# Pi_Supply_Smart_LoRa_Gateway.net
KiCad netlist of a schematic drawn in EAGLE
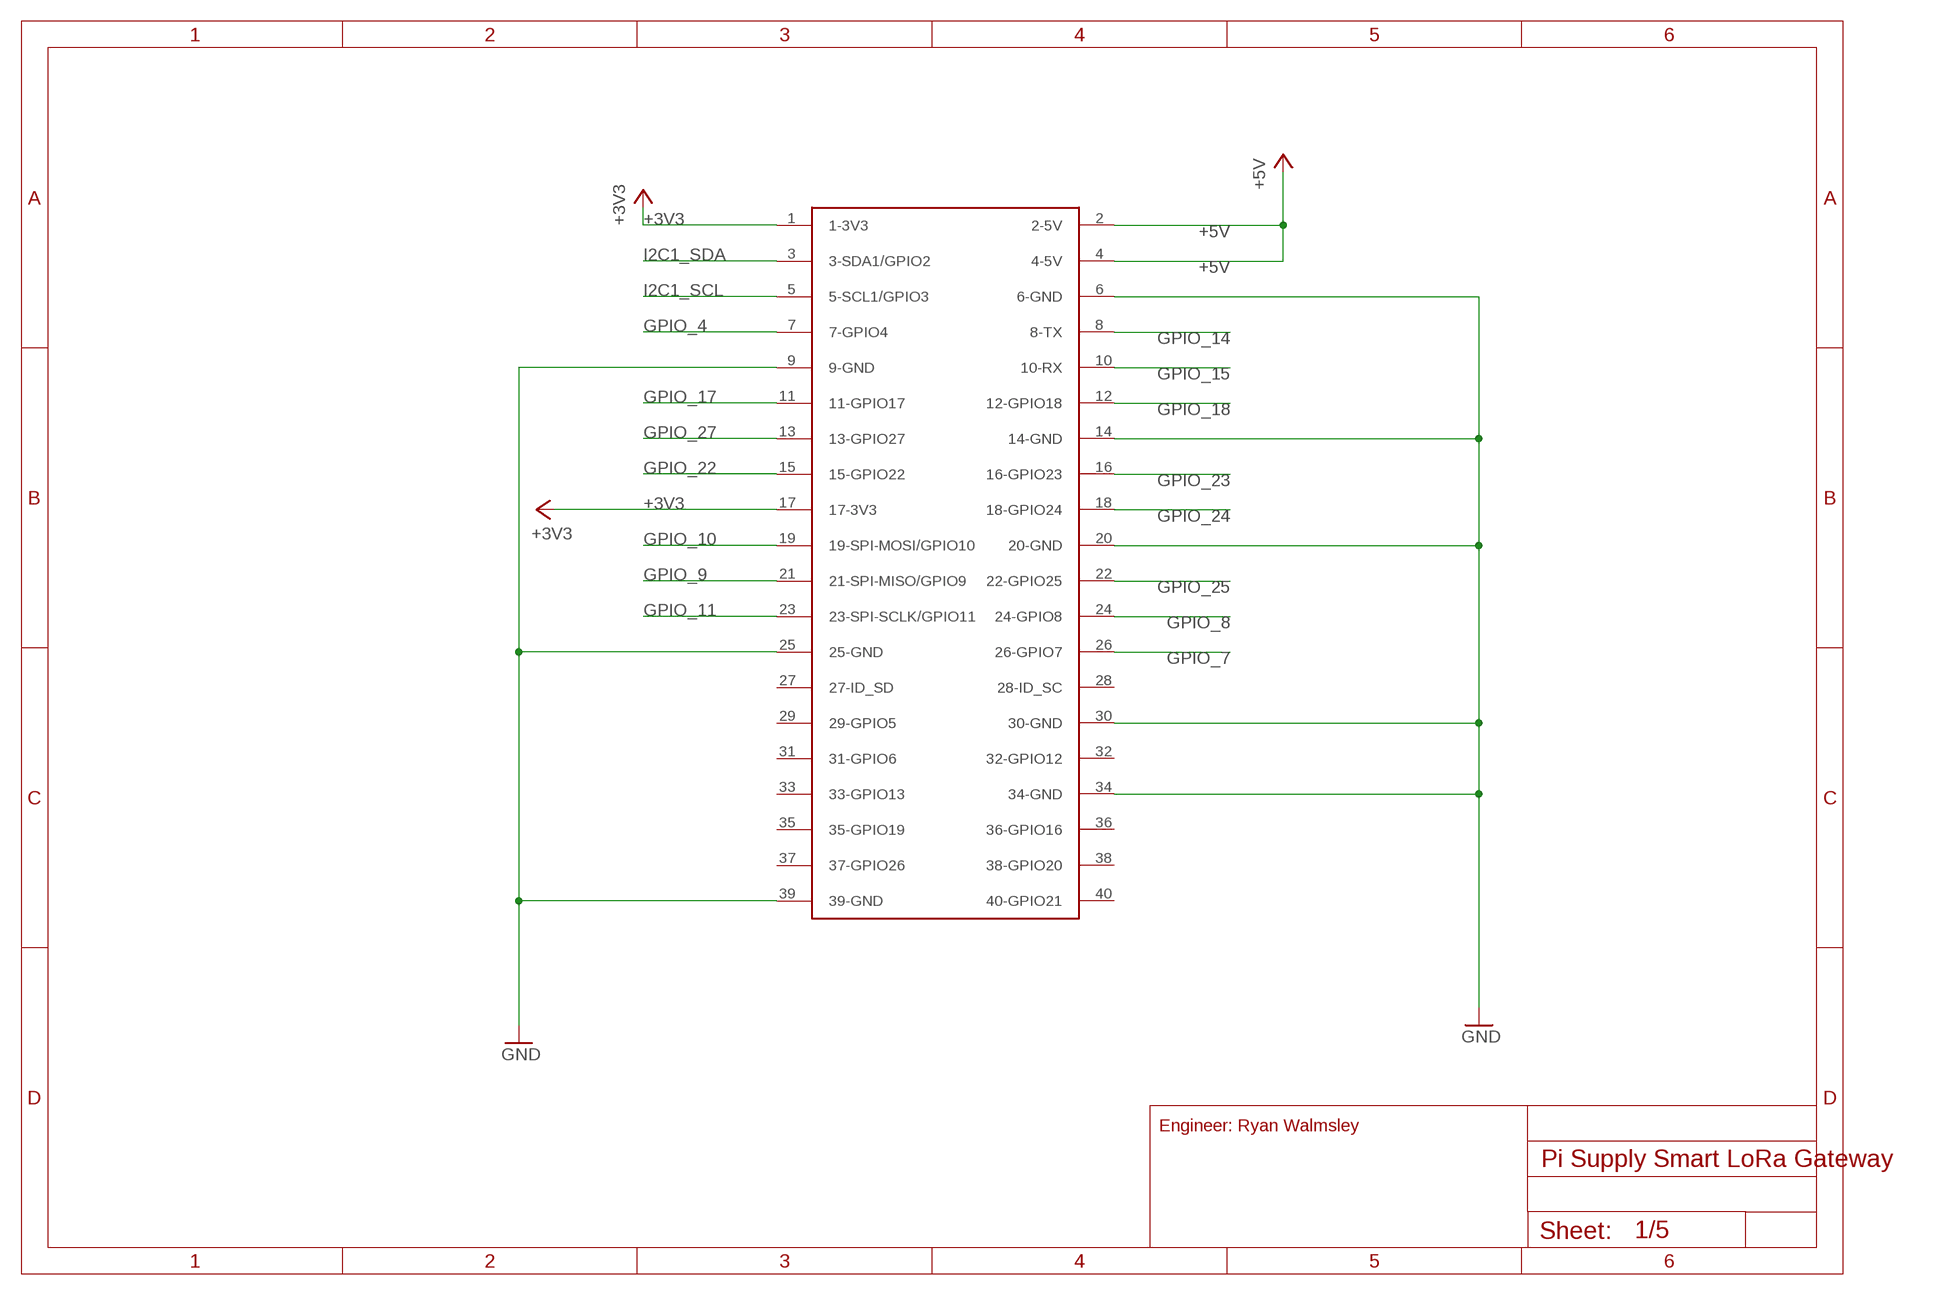
[diagram p0: schematic, sheet 1]
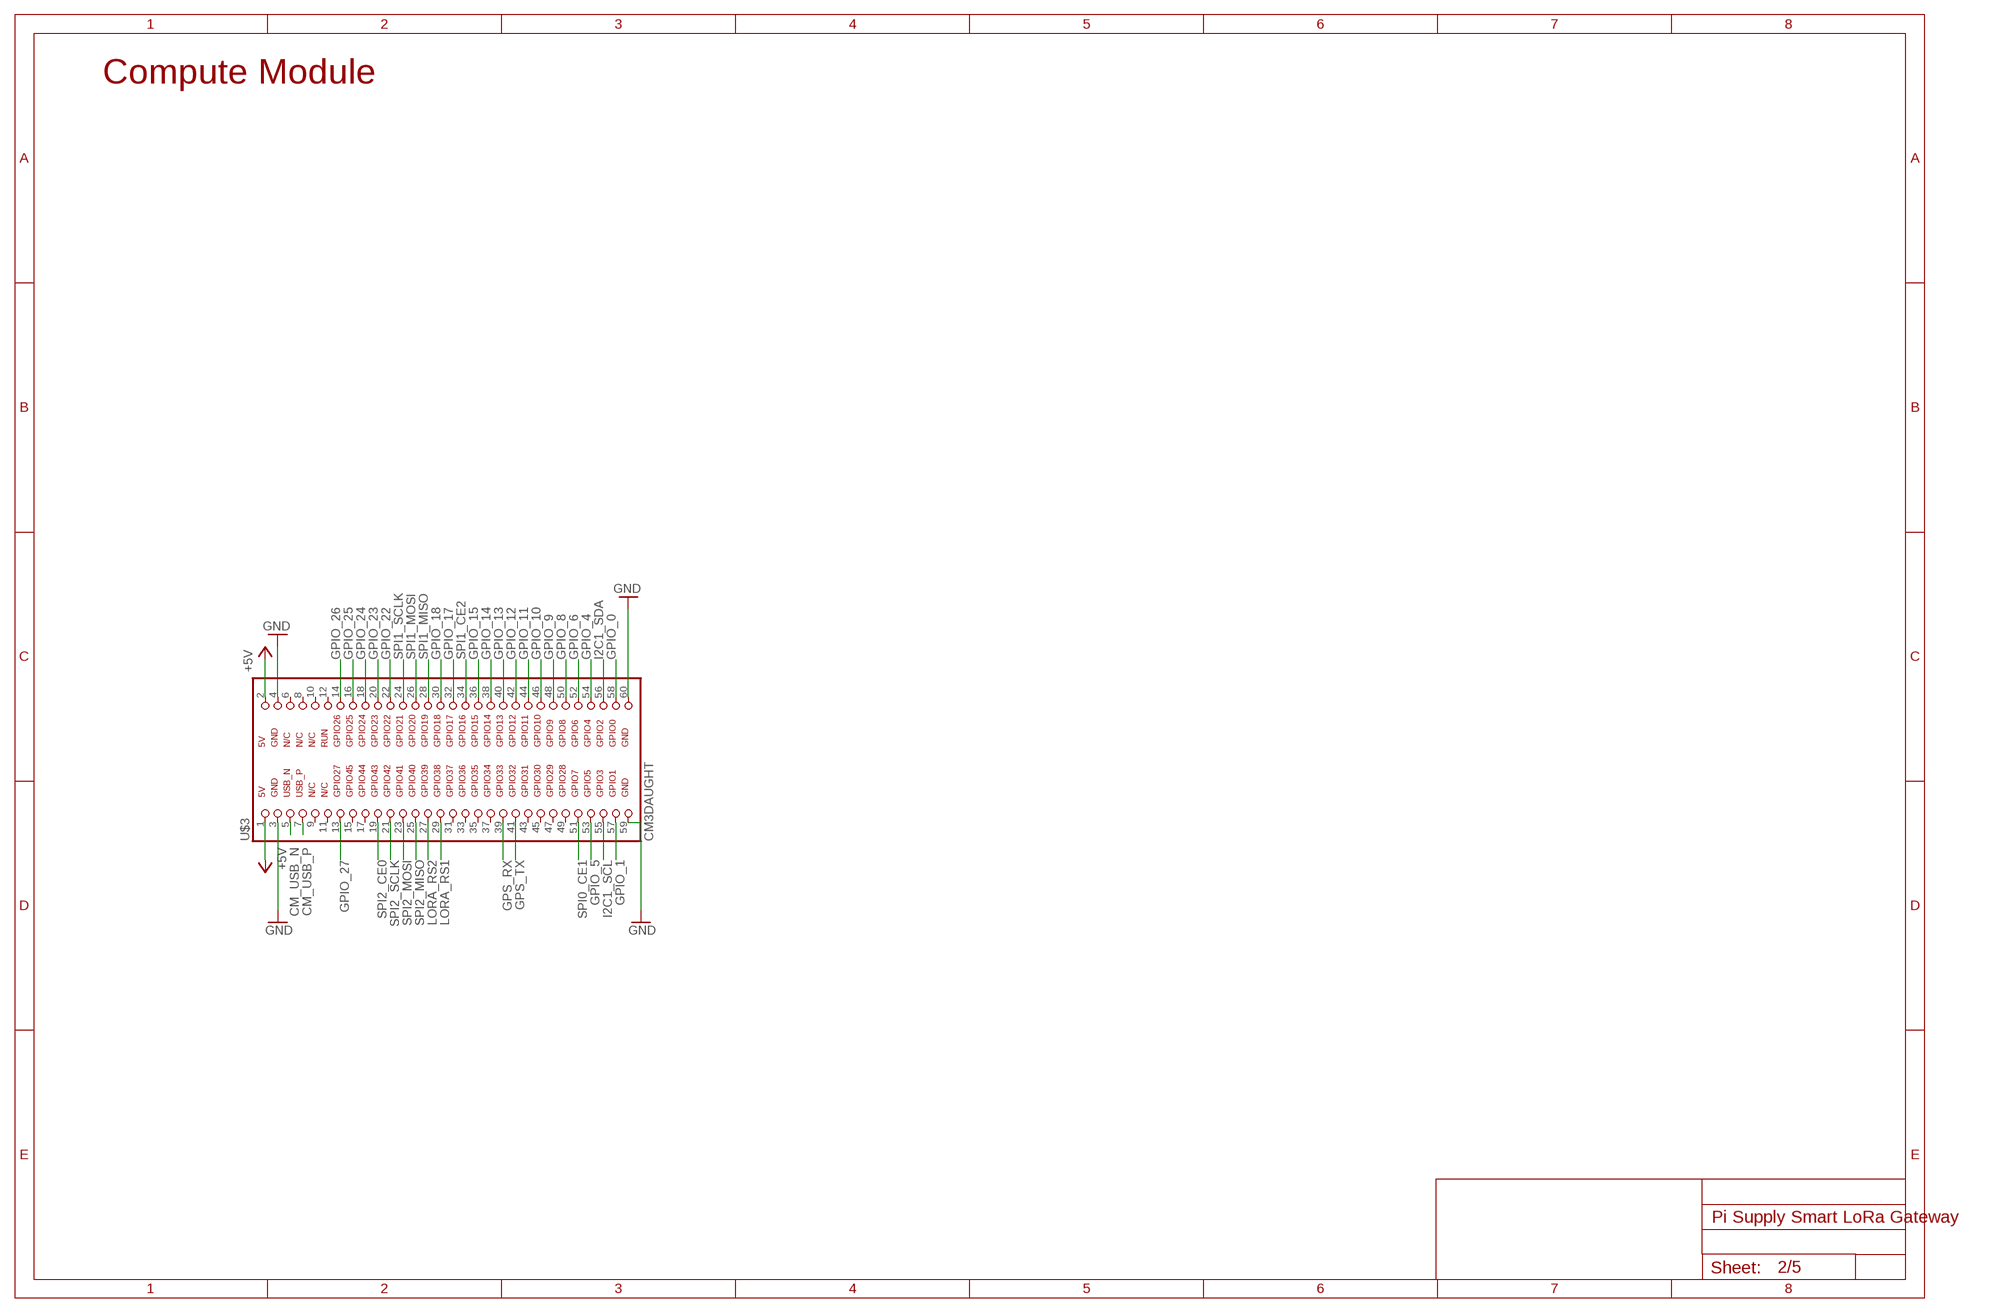
[diagram p1: schematic, sheet 2]
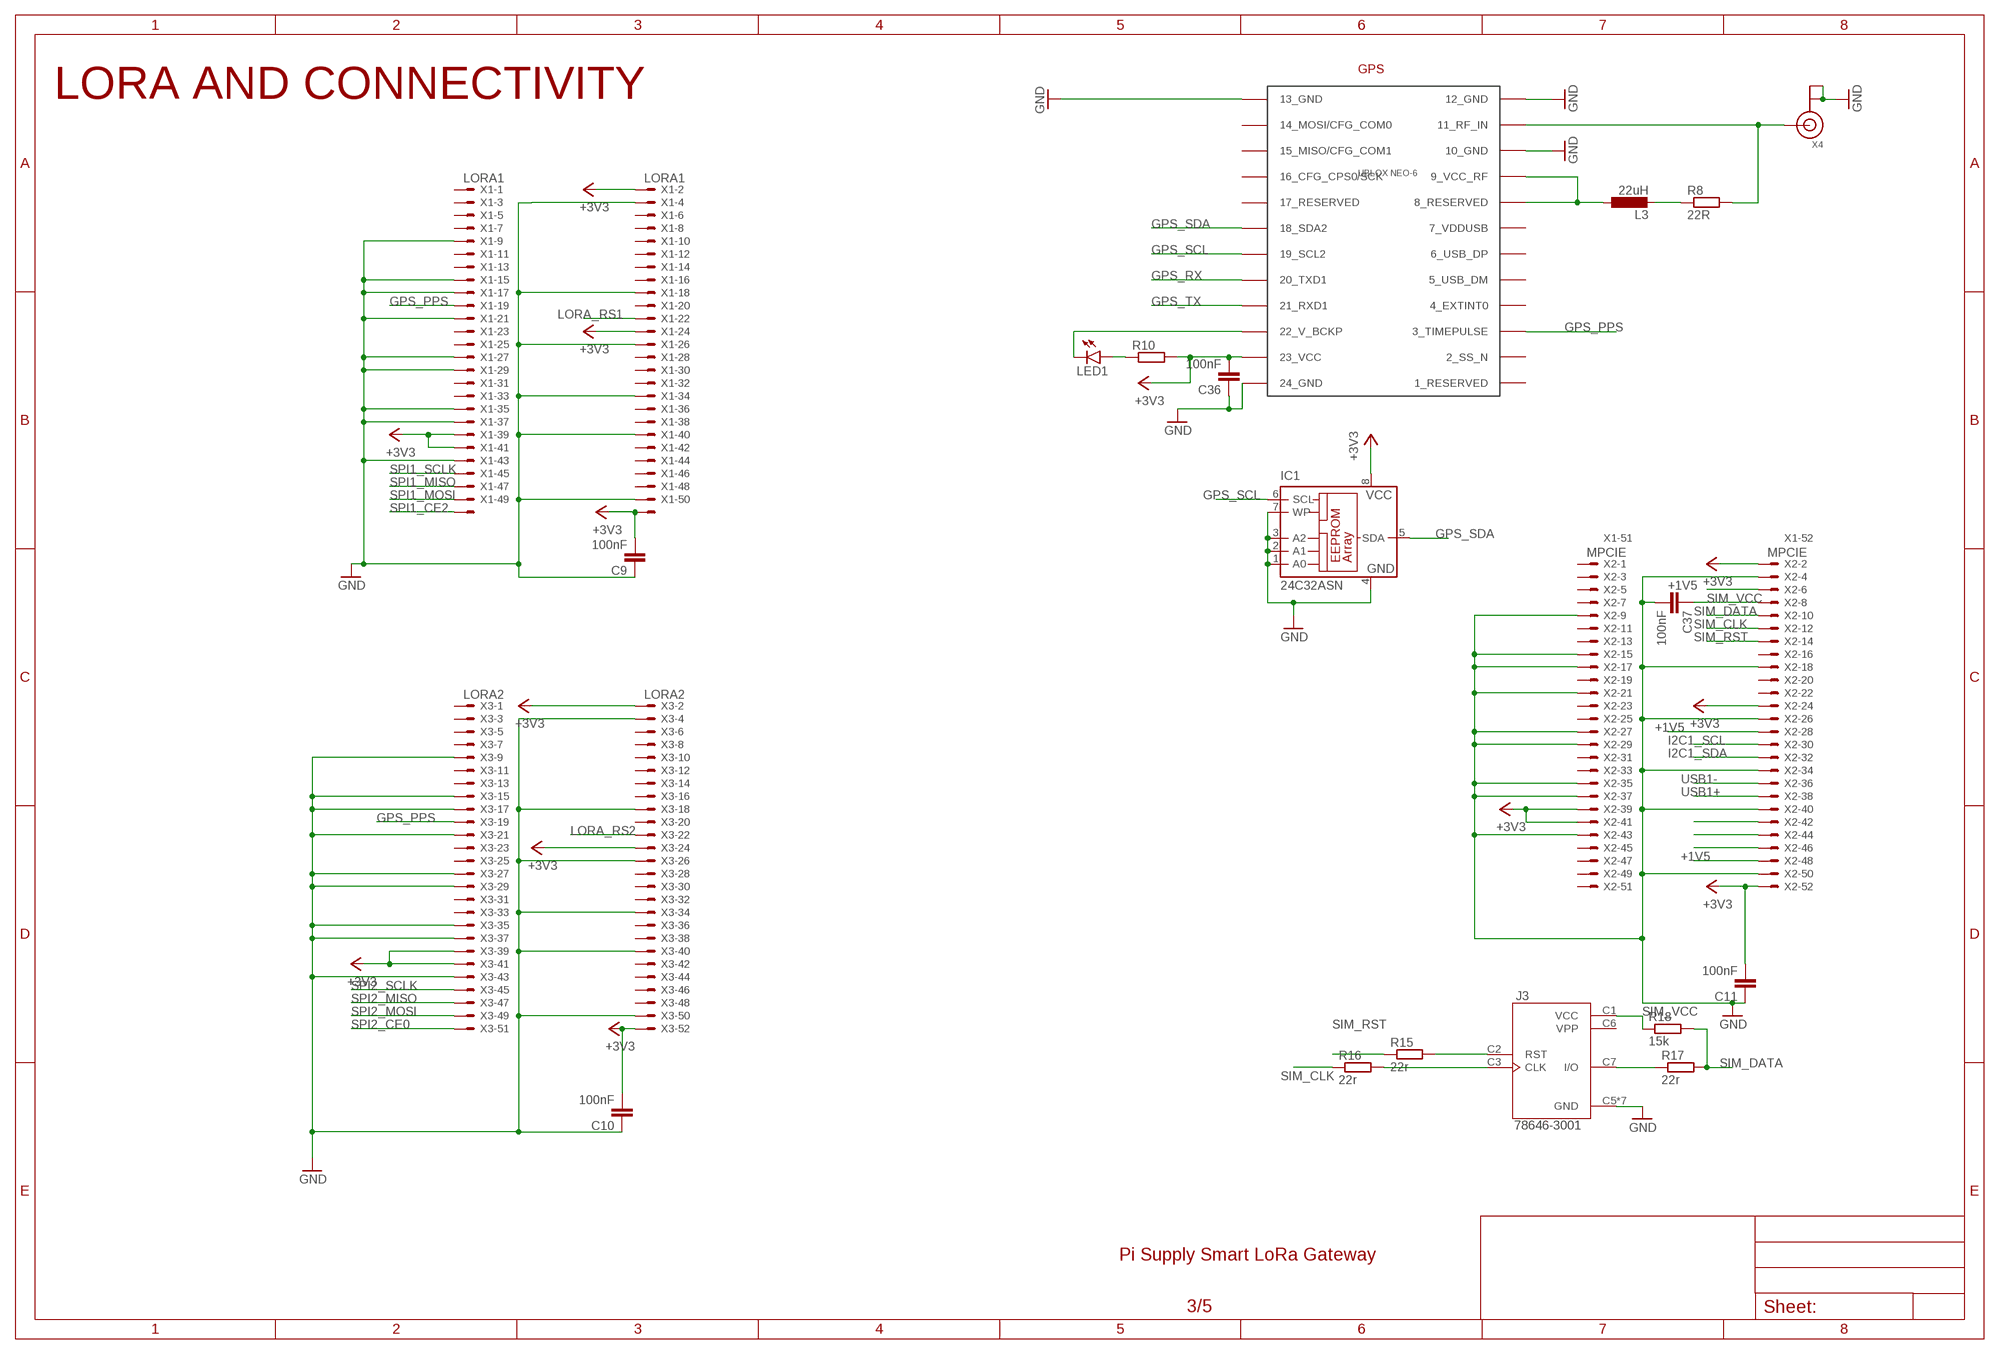
[diagram p2: schematic, sheet 3]
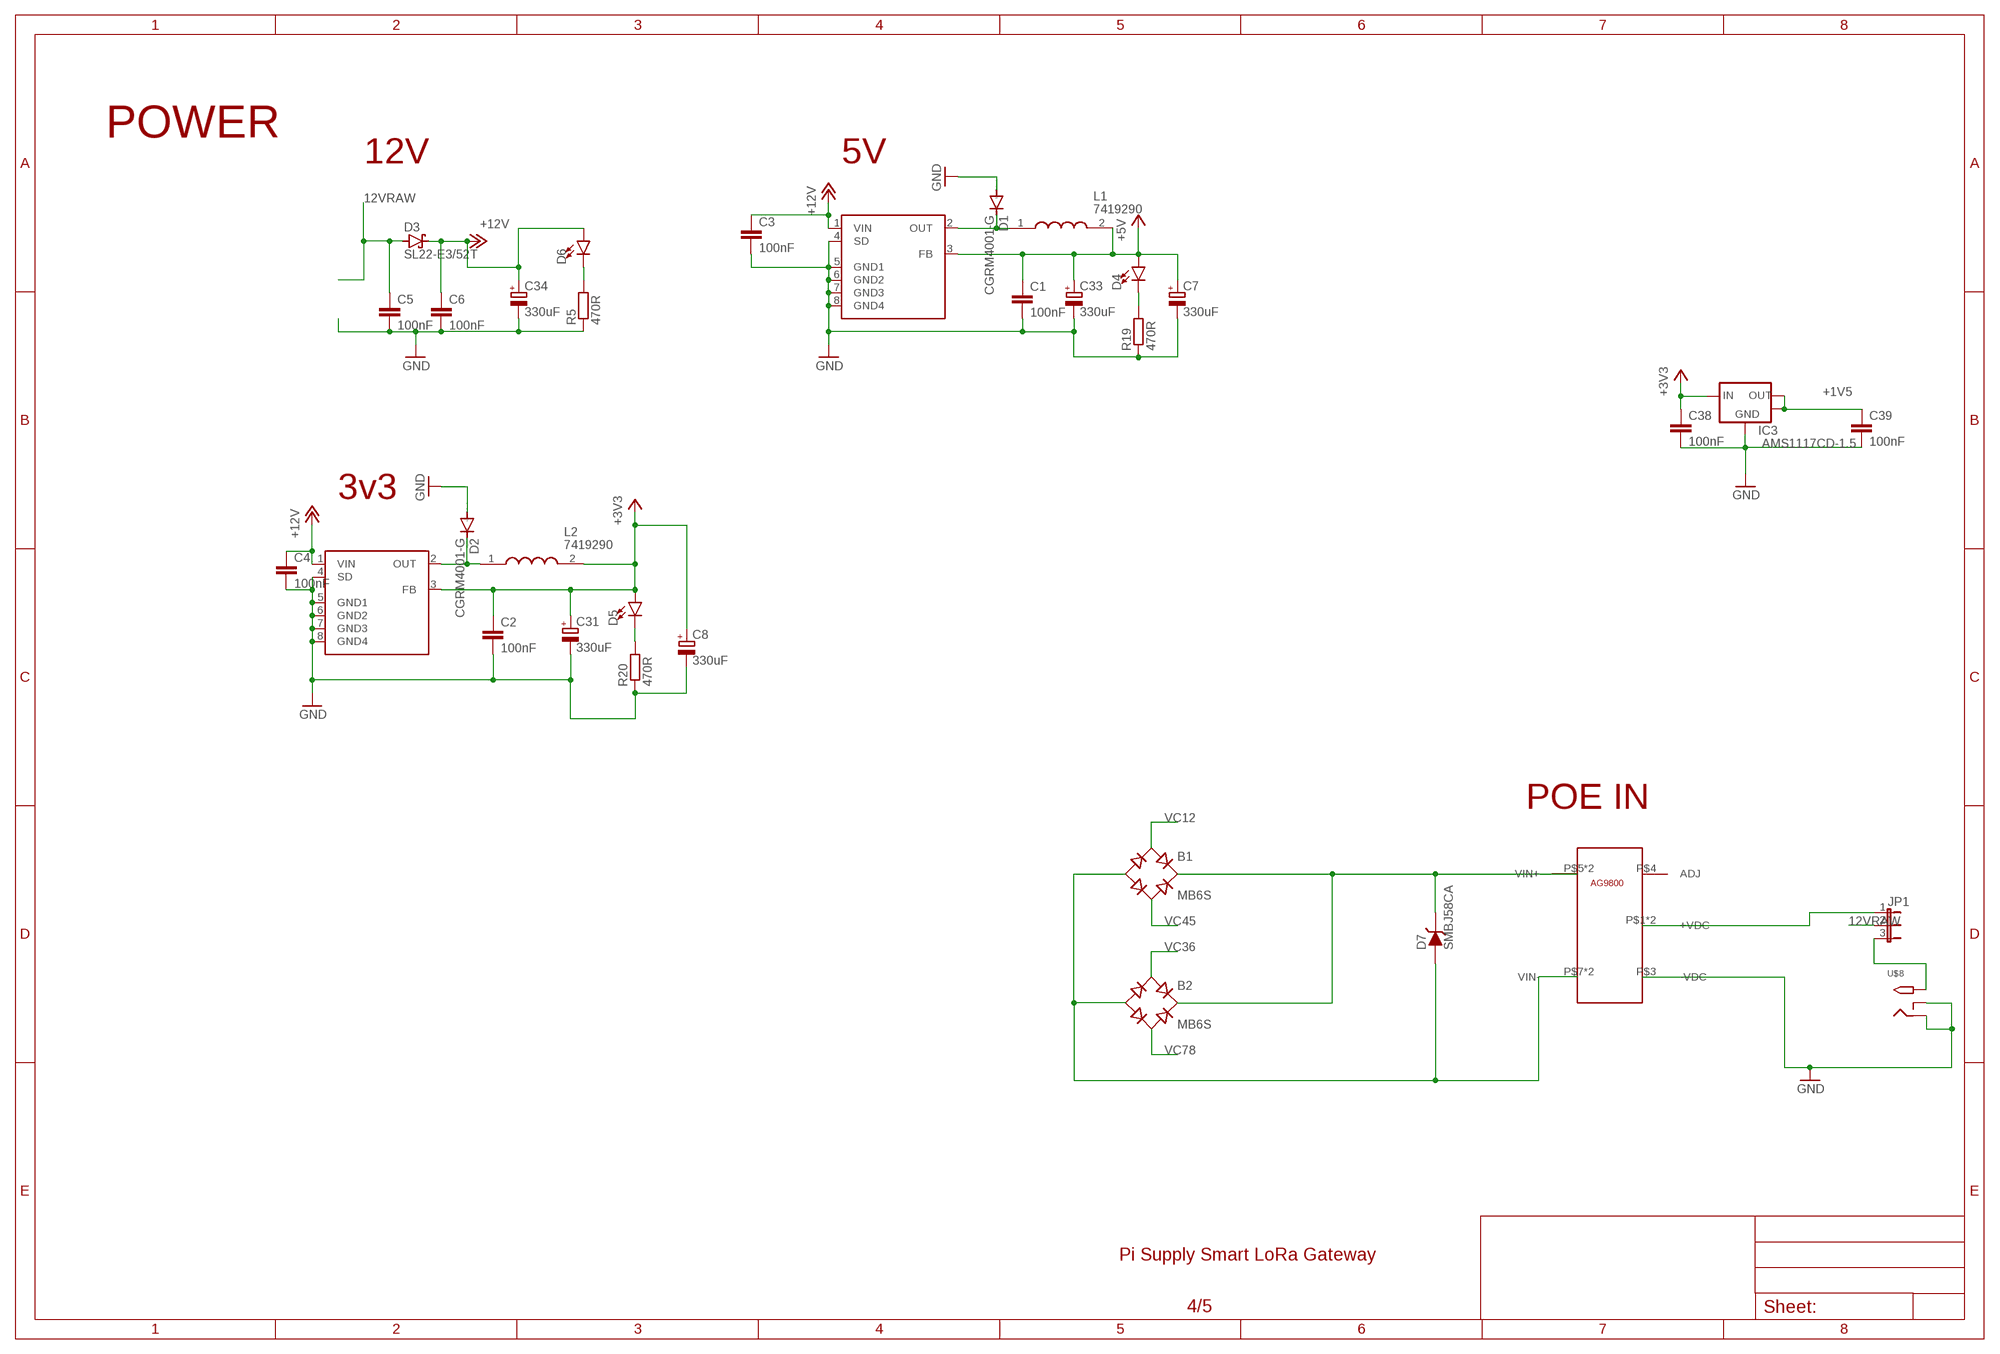
[diagram p3: schematic, sheet 4]
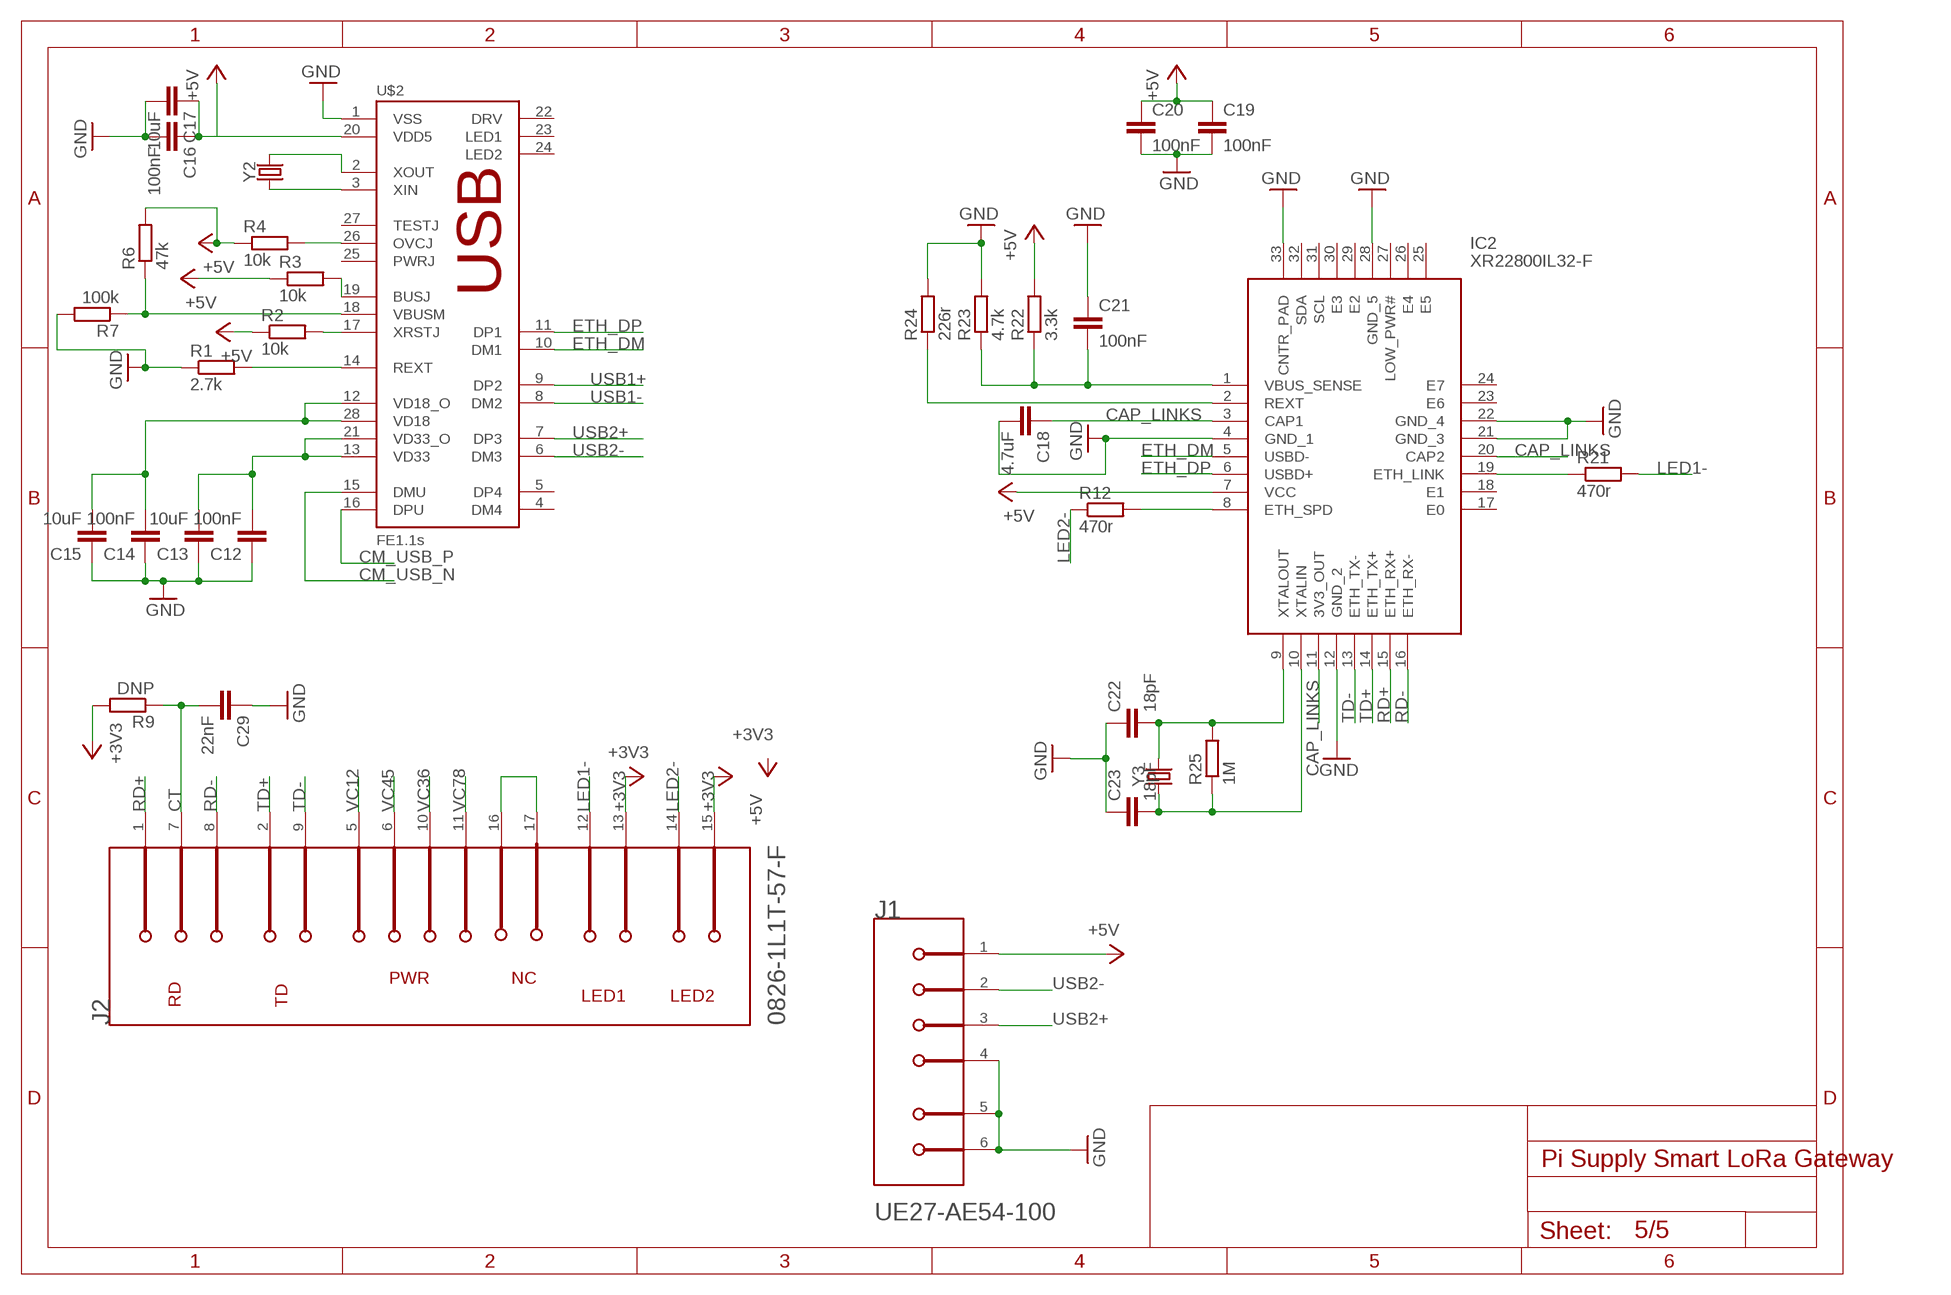
[diagram p4: schematic, sheet 5]

(export (version "E")
  (design (tool "Eeschema 10.0.6"))
  (components
    (comp (ref "C9")
      (value "100nF")
      (footprint "eagle-import:C0603")
      (libsource (lib "eagle-import") (part "resistor_348_C-EUC0603"))
    )
    (comp (ref "C10")
      (value "100nF")
      (footprint "eagle-import:C0603")
      (libsource (lib "eagle-import") (part "resistor_348_C-EUC0603"))
    )
    (comp (ref "C11")
      (value "100nF")
      (footprint "eagle-import:C0603")
      (libsource (lib "eagle-import") (part "resistor_348_C-EUC0603"))
    )
    (comp (ref "C36")
      (value "100nF")
      (footprint "eagle-import:C0603")
      (libsource (lib "eagle-import") (part "resistor_348_C-EUC0603"))
    )
    (comp (ref "C37")
      (value "100nF")
      (footprint "eagle-import:C0603")
      (libsource (lib "eagle-import") (part "resistor_348_C-EUC0603"))
    )
    (comp (ref "IC1")
      (value "24C32ASN")
      (footprint "eagle-import:SO-08")
      (fields (field (name "MPN") "IS24C32A-2GLI"))
      (libsource (lib "eagle-import") (part "24SNC32A"))
    )
    (comp (ref "J3")
      (value "78646-3001")
      (footprint "eagle-import:CONN_78646-3001")
      (fields (field (name "MF") "Molex, LLC"))
      (libsource (lib "eagle-import") (part "78646-3001"))
    )
    (comp (ref "L3")
      (value "22uH")
      (footprint "eagle-import:L2012C")
      (libsource (lib "eagle-import") (part "L-EUL2012C"))
    )
    (comp (ref "LED1")
      (value "LEDCHIPLED_0603")
      (footprint "eagle-import:CHIPLED_0603")
      (libsource (lib "eagle-import") (part "LEDCHIPLED_0603"))
    )
    (comp (ref "R8")
      (value "22R")
      (footprint "eagle-import:R0603")
      (libsource (lib "eagle-import") (part "resistor_348_R-EU_R0603"))
    )
    (comp (ref "R10")
      (value "R-EU_R0603")
      (footprint "eagle-import:R0603")
      (libsource (lib "eagle-import") (part "resistor_348_R-EU_R0603"))
    )
    (comp (ref "R15")
      (value "22r")
      (footprint "eagle-import:R0603")
      (libsource (lib "eagle-import") (part "resistor_348_R-EU_R0603"))
    )
    (comp (ref "R16")
      (value "22r")
      (footprint "eagle-import:R0603")
      (libsource (lib "eagle-import") (part "resistor_348_R-EU_R0603"))
    )
    (comp (ref "R17")
      (value "22r")
      (footprint "eagle-import:R0603")
      (libsource (lib "eagle-import") (part "resistor_348_R-EU_R0603"))
    )
    (comp (ref "R18")
      (value "15k")
      (footprint "eagle-import:R0603")
      (libsource (lib "eagle-import") (part "resistor_348_R-EU_R0603"))
    )
    (comp (ref "U$4")
      (value "UBLOX_NEO-6")
      (footprint "eagle-import:UBLOX_NEO-6P")
      (libsource (lib "eagle-import") (part "UBLOX_NEO-6"))
    )
    (comp (ref "X1")
      (value "LORA1")
      (footprint "eagle-import:679105700")
      (fields (field (name "MPN") "67910-5700"))
      (libsource (lib "eagle-import") (part "679105700"))
    )
    (comp (ref "X2")
      (value "MPCIE")
      (footprint "eagle-import:679105700")
      (fields (field (name "MPN") "67910-5700"))
      (libsource (lib "eagle-import") (part "679105700"))
    )
    (comp (ref "X3")
      (value "LORA2")
      (footprint "eagle-import:679105700")
      (fields (field (name "MPN") "67910-5700"))
      (libsource (lib "eagle-import") (part "679105700"))
    )
    (comp (ref "X4")
      (value "ANTENNA_U.FL")
      (footprint "eagle-import:U.FL")
      (libsource (lib "eagle-import") (part "ANTENNA_U.FL"))
    )
    (comp (ref "U$5")
      (value "RASPBERRY-PI+NONOTCHES")
      (footprint "eagle-import:RASPBERRY-PI-PLUS")
      (libsource (lib "eagle-import") (part "RASPBERRY-PI+NONOTCHES"))
    )
    (comp (ref "B1")
      (value "MB6S")
      (footprint "eagle-import:SOIC-4")
      (libsource (lib "eagle-import") (part "MBS6"))
    )
    (comp (ref "B2")
      (value "MB6S")
      (footprint "eagle-import:SOIC-4")
      (libsource (lib "eagle-import") (part "MBS6"))
    )
    (comp (ref "C1")
      (value "100nF")
      (footprint "eagle-import:C0603")
      (libsource (lib "eagle-import") (part "resistor_348_C-EUC0603"))
    )
    (comp (ref "C2")
      (value "100nF")
      (footprint "eagle-import:C0603")
      (libsource (lib "eagle-import") (part "resistor_348_C-EUC0603"))
    )
    (comp (ref "C3")
      (value "100nF")
      (footprint "eagle-import:C0603")
      (libsource (lib "eagle-import") (part "resistor_348_C-EUC0603"))
    )
    (comp (ref "C4")
      (value "100nF")
      (footprint "eagle-import:C0603")
      (libsource (lib "eagle-import") (part "resistor_348_C-EUC0603"))
    )
    (comp (ref "C5")
      (value "100nF")
      (footprint "eagle-import:C0603")
      (libsource (lib "eagle-import") (part "resistor_348_C-EUC0603"))
    )
    (comp (ref "C6")
      (value "100nF")
      (footprint "eagle-import:C0603")
      (libsource (lib "eagle-import") (part "resistor_348_C-EUC0603"))
    )
    (comp (ref "C7")
      (value "330uF")
      (footprint "eagle-import:PANASONIC_E")
      (libsource (lib "eagle-import") (part "CPOL-EUE"))
    )
    (comp (ref "C8")
      (value "330uF")
      (footprint "eagle-import:PANASONIC_E")
      (libsource (lib "eagle-import") (part "CPOL-EUE"))
    )
    (comp (ref "C31")
      (value "330uF")
      (footprint "eagle-import:PANASONIC_E")
      (libsource (lib "eagle-import") (part "CPOL-EUE"))
    )
    (comp (ref "C33")
      (value "330uF")
      (footprint "eagle-import:PANASONIC_E")
      (libsource (lib "eagle-import") (part "CPOL-EUE"))
    )
    (comp (ref "C34")
      (value "330uF")
      (footprint "eagle-import:PANASONIC_E")
      (libsource (lib "eagle-import") (part "CPOL-EUE"))
    )
    (comp (ref "C38")
      (value "100nF")
      (footprint "eagle-import:C0603")
      (libsource (lib "eagle-import") (part "resistor_348_C-EUC0603"))
    )
    (comp (ref "C39")
      (value "100nF")
      (footprint "eagle-import:C0603")
      (libsource (lib "eagle-import") (part "resistor_348_C-EUC0603"))
    )
    (comp (ref "D1")
      (value "CGRM4001-G")
      (footprint "eagle-import:SOD-123_MINI-SMA")
      (libsource (lib "eagle-import") (part "CGRM400-G1"))
    )
    (comp (ref "D2")
      (value "CGRM4001-G")
      (footprint "eagle-import:SOD-123_MINI-SMA")
      (libsource (lib "eagle-import") (part "CGRM400-G1"))
    )
    (comp (ref "D3")
      (value "SL22-E3/52T")
      (footprint "eagle-import:SMB")
      (libsource (lib "eagle-import") (part "SCHOTTKY-DIODESMD"))
    )
    (comp (ref "D4")
      (value "LED0603")
      (footprint "eagle-import:LED-0603")
      (libsource (lib "eagle-import") (part "LED0603"))
    )
    (comp (ref "D5")
      (value "LED0603")
      (footprint "eagle-import:LED-0603")
      (libsource (lib "eagle-import") (part "LED0603"))
    )
    (comp (ref "D6")
      (value "LED0603")
      (footprint "eagle-import:LED-0603")
      (libsource (lib "eagle-import") (part "LED0603"))
    )
    (comp (ref "D7")
      (value "SMBJ58CA")
      (footprint "eagle-import:DO-214AA")
      (libsource (lib "eagle-import") (part "P6SMBXXAT3GSMA"))
    )
    (comp (ref "IC3")
      (value "AMS1117CD-1.5")
      (footprint "eagle-import:SOT-223-3")
      (libsource (lib "eagle-import") (part "LM1117-SOT223"))
    )
    (comp (ref "JP1")
      (value "JP2E")
      (footprint "eagle-import:JP2")
      (libsource (lib "eagle-import") (part "JP2E"))
    )
    (comp (ref "L1")
      (value "7419290")
      (footprint "eagle-import:INDPM115100X410N")
      (libsource (lib "eagle-import") (part "7419290"))
    )
    (comp (ref "L2")
      (value "7419290")
      (footprint "eagle-import:INDPM115100X410N")
      (libsource (lib "eagle-import") (part "7419290"))
    )
    (comp (ref "R5")
      (value "470R")
      (footprint "eagle-import:R0603")
      (libsource (lib "eagle-import") (part "resistor_348_R-EU_R0603"))
    )
    (comp (ref "R19")
      (value "470R")
      (footprint "eagle-import:R0603")
      (libsource (lib "eagle-import") (part "resistor_348_R-EU_R0603"))
    )
    (comp (ref "R20")
      (value "470R")
      (footprint "eagle-import:R0603")
      (libsource (lib "eagle-import") (part "resistor_348_R-EU_R0603"))
    )
    (comp (ref "U$1")
      (value "AG9800")
      (footprint "eagle-import:AG9800")
      (libsource (lib "eagle-import") (part "AG9800"))
    )
    (comp (ref "U$8")
      (value "2.1MMJACKSMT")
      (footprint "eagle-import:DCJACK_2MM_SMT")
      (libsource (lib "eagle-import") (part "2.1MMJACKSMT"))
    )
    (comp (ref "U1")
      (value "AP1509")
      (footprint "eagle-import:SO08")
      (libsource (lib "eagle-import") (part "AP1509"))
    )
    (comp (ref "U2")
      (value "AP1509-50")
      (footprint "eagle-import:SO08")
      (libsource (lib "eagle-import") (part "AP1509"))
    )
    (comp (ref "C12")
      (value "100nF")
      (footprint "eagle-import:C0603")
      (libsource (lib "eagle-import") (part "C-EUC0603"))
    )
    (comp (ref "C13")
      (value "10uF")
      (footprint "eagle-import:C0603")
      (libsource (lib "eagle-import") (part "C-EUC0603"))
    )
    (comp (ref "C14")
      (value "100nF")
      (footprint "eagle-import:C0603")
      (libsource (lib "eagle-import") (part "C-EUC0603"))
    )
    (comp (ref "C15")
      (value "10uF")
      (footprint "eagle-import:C0603")
      (libsource (lib "eagle-import") (part "C-EUC0603"))
    )
    (comp (ref "C16")
      (value "100nF")
      (footprint "eagle-import:C0603")
      (libsource (lib "eagle-import") (part "C-EUC0603"))
    )
    (comp (ref "C17")
      (value "10uF")
      (footprint "eagle-import:C0603")
      (libsource (lib "eagle-import") (part "C-EUC0603"))
    )
    (comp (ref "C18")
      (value "4.7uF")
      (footprint "eagle-import:C0603")
      (libsource (lib "eagle-import") (part "C-EUC0603"))
    )
    (comp (ref "C19")
      (value "100nF")
      (footprint "eagle-import:C0603")
      (libsource (lib "eagle-import") (part "C-EUC0603"))
    )
    (comp (ref "C20")
      (value "100nF")
      (footprint "eagle-import:C0603")
      (libsource (lib "eagle-import") (part "C-EUC0603"))
    )
    (comp (ref "C21")
      (value "100nF")
      (footprint "eagle-import:C0603")
      (libsource (lib "eagle-import") (part "C-EUC0603"))
    )
    (comp (ref "C22")
      (value "18pF")
      (footprint "eagle-import:C0603")
      (libsource (lib "eagle-import") (part "C-EUC0603"))
    )
    (comp (ref "C23")
      (value "18pF")
      (footprint "eagle-import:C0603")
      (libsource (lib "eagle-import") (part "C-EUC0603"))
    )
    (comp (ref "C29")
      (value "22nF")
      (footprint "eagle-import:C0603")
      (libsource (lib "eagle-import") (part "resistor_348_C-EUC0603"))
    )
    (comp (ref "IC2")
      (value "XR22800IL32-F")
      (footprint "eagle-import:QFN50P500X500X100-33N")
      (fields (field (name "MOUSER_PART_NUMBER") "701-22800IL32-F"))
      (libsource (lib "eagle-import") (part "XR22800IL32-F"))
    )
    (comp (ref "J1")
      (value "AMPHENOL_UE27-AE54-100AMPHENOL_UE27-AE54-100_0_0")
      (footprint "eagle-import:AMPHENOL_UE27-AE54-100_0")
      (fields
        (field (name "DIGIKEY_PART_NUMBER") "UE27AE54100-ND")
        (field (name "MF") "Amphenol")
        (field (name "MOUSER_PART_NUMBER") "523-UE27-AE54-100")
      )
      (libsource (lib "eagle-import") (part "AMPHENOL_UE27-AE54-100AMPHENOL_UE27-AE54-100_0_0"))
    )
    (comp (ref "J2")
      (value "TRJK1014A8NL")
      (footprint "eagle-import:BEL_0826-1L1T-57-F_0")
      (fields
        (field (name "DIGIKEY_PART_NUMBER") "507-1431-ND")
        (field (name "MF") "Bel")
        (field (name "MOUSER_PART_NUMBER") "530-0826-1L1T-57-F")
      )
      (libsource (lib "eagle-import") (part "BEL_0826-1L1T-57-FBEL_0826-1L1T-57-F_0_0"))
    )
    (comp (ref "R1")
      (value "2.7k")
      (footprint "eagle-import:R0603")
      (libsource (lib "eagle-import") (part "R-EU_R0603"))
    )
    (comp (ref "R2")
      (value "10k")
      (footprint "eagle-import:R0603")
      (libsource (lib "eagle-import") (part "R-EU_R0603"))
    )
    (comp (ref "R3")
      (value "10k")
      (footprint "eagle-import:R0603")
      (libsource (lib "eagle-import") (part "R-EU_R0603"))
    )
    (comp (ref "R4")
      (value "10k")
      (footprint "eagle-import:R0603")
      (libsource (lib "eagle-import") (part "R-EU_R0603"))
    )
    (comp (ref "R6")
      (value "47k")
      (footprint "eagle-import:R0603")
      (libsource (lib "eagle-import") (part "R-EU_R0603"))
    )
    (comp (ref "R7")
      (value "100k")
      (footprint "eagle-import:R0603")
      (libsource (lib "eagle-import") (part "R-EU_R0603"))
    )
    (comp (ref "R9")
      (value "DNP")
      (footprint "eagle-import:R0603")
      (libsource (lib "eagle-import") (part "resistor_348_R-EU_R0603"))
    )
    (comp (ref "R12")
      (value "470r")
      (footprint "eagle-import:R0603")
      (libsource (lib "eagle-import") (part "R-EU_R0603"))
    )
    (comp (ref "R21")
      (value "470r")
      (footprint "eagle-import:R0603")
      (libsource (lib "eagle-import") (part "R-EU_R0603"))
    )
    (comp (ref "R22")
      (value "3.3k")
      (footprint "eagle-import:R0603")
      (libsource (lib "eagle-import") (part "R-EU_R0603"))
    )
    (comp (ref "R23")
      (value "4.7k")
      (footprint "eagle-import:R0603")
      (libsource (lib "eagle-import") (part "R-EU_R0603"))
    )
    (comp (ref "R24")
      (value "226r")
      (footprint "eagle-import:R0603")
      (libsource (lib "eagle-import") (part "R-EU_R0603"))
    )
    (comp (ref "R25")
      (value "1M")
      (footprint "eagle-import:R0603")
      (libsource (lib "eagle-import") (part "R-EU_R0603"))
    )
    (comp (ref "U$2")
      (value "FE1.1S")
      (footprint "eagle-import:FE1.1S_SSOP-28")
      (libsource (lib "eagle-import") (part "FE1.1S"))
    )
    (comp (ref "Y2")
      (value "12mHZ")
      (footprint "eagle-import:HC49UP")
      (libsource (lib "eagle-import") (part "CRYSTALSMD-HC49UP"))
    )
    (comp (ref "Y3")
      (value "25Mhz")
      (footprint "eagle-import:HC49UP")
      (libsource (lib "eagle-import") (part "CRYSTALSMD-HC49UP"))
    )
    (comp (ref "U$3")
      (value "CM3DAUGHT")
      (footprint "eagle-import:2X30")
      (libsource (lib "eagle-import") (part "CM3DAUGHT"))
    )
  )
  (nets
    (net (code "1") (name "+1V5") (class "Default")
      (node (ref "C39") (pin "1") (pinfunction "1_1") (pintype "passive"))
      (node (ref "IC3") (pin "2") (pinfunction "VOUT_2") (pintype "bidirectional"))
      (node (ref "IC3") (pin "4") (pinfunction "HEATSINK_4") (pintype "bidirectional"))
      (node (ref "X2") (pin "28") (pinfunction "S_28") (pintype "passive"))
      (node (ref "X2") (pin "48") (pinfunction "S_48") (pintype "passive"))
      (node (ref "X2") (pin "6") (pinfunction "S_6") (pintype "passive"))
    )
    (net (code "2") (name "+3V3") (class "Default")
      (node (ref "C10") (pin "2") (pinfunction "2_2") (pintype "passive"))
      (node (ref "C11") (pin "2") (pinfunction "2_2") (pintype "passive"))
      (node (ref "C2") (pin "1") (pinfunction "1_1") (pintype "passive"))
      (node (ref "C31") (pin "+") (pinfunction "+_+") (pintype "passive"))
      (node (ref "C36") (pin "2") (pinfunction "2_2") (pintype "passive"))
      (node (ref "C38") (pin "1") (pinfunction "1_1") (pintype "passive"))
      (node (ref "C8") (pin "+") (pinfunction "+_+") (pintype "passive"))
      (node (ref "C9") (pin "2") (pinfunction "2_2") (pintype "passive"))
      (node (ref "D5") (pin "A") (pinfunction "A_A") (pintype "passive"))
      (node (ref "IC1") (pin "8") (pinfunction "VCC_8") (pintype "power_in"))
      (node (ref "IC3") (pin "3") (pinfunction "VIN_3") (pintype "bidirectional"))
      (node (ref "J2") (pin "13") (pinfunction "2_LED1_13") (pintype "passive"))
      (node (ref "J2") (pin "15") (pinfunction "LED2_ANODE_15") (pintype "passive"))
      (node (ref "L2") (pin "2") (pinfunction "2_2") (pintype "bidirectional"))
      (node (ref "R10") (pin "2") (pinfunction "2_2") (pintype "passive"))
      (node (ref "R9") (pin "2") (pinfunction "2_2") (pintype "passive"))
      (node (ref "U$4") (pin "23_VCC") (pinfunction "23_VCC_23_VCC") (pintype "bidirectional"))
      (node (ref "U$5") (pin "1") (pinfunction "1-3V3_1") (pintype "bidirectional"))
      (node (ref "U$5") (pin "17") (pinfunction "17-3V3_17") (pintype "bidirectional"))
      (node (ref "U1") (pin "3") (pinfunction "FB_3") (pintype "input"))
      (node (ref "X1") (pin "2") (pinfunction "S_2") (pintype "passive"))
      (node (ref "X1") (pin "24") (pinfunction "S_24") (pintype "passive"))
      (node (ref "X1") (pin "39") (pinfunction "S_39") (pintype "passive"))
      (node (ref "X1") (pin "41") (pinfunction "S_41") (pintype "passive"))
      (node (ref "X1") (pin "52") (pinfunction "S_52") (pintype "passive"))
      (node (ref "X2") (pin "2") (pinfunction "S_2") (pintype "passive"))
      (node (ref "X2") (pin "24") (pinfunction "S_24") (pintype "passive"))
      (node (ref "X2") (pin "39") (pinfunction "S_39") (pintype "passive"))
      (node (ref "X2") (pin "41") (pinfunction "S_41") (pintype "passive"))
      (node (ref "X2") (pin "52") (pinfunction "S_52") (pintype "passive"))
      (node (ref "X3") (pin "2") (pinfunction "S_2") (pintype "passive"))
      (node (ref "X3") (pin "24") (pinfunction "S_24") (pintype "passive"))
      (node (ref "X3") (pin "39") (pinfunction "S_39") (pintype "passive"))
      (node (ref "X3") (pin "41") (pinfunction "S_41") (pintype "passive"))
      (node (ref "X3") (pin "52") (pinfunction "S_52") (pintype "passive"))
    )
    (net (code "3") (name "+5V") (class "Default")
      (node (ref "C1") (pin "1") (pinfunction "1_1") (pintype "passive"))
      (node (ref "C16") (pin "1") (pinfunction "1_1") (pintype "passive"))
      (node (ref "C17") (pin "1") (pinfunction "1_1") (pintype "passive"))
      (node (ref "C19") (pin "1") (pinfunction "1_1") (pintype "passive"))
      (node (ref "C20") (pin "1") (pinfunction "1_1") (pintype "passive"))
      (node (ref "C33") (pin "+") (pinfunction "+_+") (pintype "passive"))
      (node (ref "C7") (pin "+") (pinfunction "+_+") (pintype "passive"))
      (node (ref "D4") (pin "A") (pinfunction "A_A") (pintype "passive"))
      (node (ref "IC2") (pin "7") (pinfunction "VCC_7") (pintype "bidirectional"))
      (node (ref "J1") (pin "1") (pinfunction "1_1") (pintype "passive"))
      (node (ref "L1") (pin "2") (pinfunction "2_2") (pintype "bidirectional"))
      (node (ref "R2") (pin "1") (pinfunction "1_1") (pintype "passive"))
      (node (ref "R22") (pin "2") (pinfunction "2_2") (pintype "passive"))
      (node (ref "R3") (pin "1") (pinfunction "1_1") (pintype "passive"))
      (node (ref "R4") (pin "1") (pinfunction "1_1") (pintype "passive"))
      (node (ref "R6") (pin "2") (pinfunction "2_2") (pintype "passive"))
      (node (ref "U$2") (pin "20") (pinfunction "VDD5_20") (pintype "bidirectional"))
      (node (ref "U$3") (pin "1") (pinfunction "5V_1") (pintype "power_in"))
      (node (ref "U$3") (pin "2") (pinfunction "5V_2") (pintype "power_in"))
      (node (ref "U$5") (pin "2") (pinfunction "2-5V_2") (pintype "bidirectional"))
      (node (ref "U$5") (pin "4") (pinfunction "4-5V_4") (pintype "bidirectional"))
      (node (ref "U2") (pin "3") (pinfunction "FB_3") (pintype "input"))
    )
    (net (code "4") (name "+12V") (class "Default")
      (node (ref "C3") (pin "1") (pinfunction "1_1") (pintype "passive"))
      (node (ref "C34") (pin "+") (pinfunction "+_+") (pintype "passive"))
      (node (ref "C4") (pin "1") (pinfunction "1_1") (pintype "passive"))
      (node (ref "C6") (pin "1") (pinfunction "1_1") (pintype "passive"))
      (node (ref "D3") (pin "C") (pinfunction "C_C") (pintype "passive"))
      (node (ref "D6") (pin "A") (pinfunction "A_A") (pintype "passive"))
      (node (ref "U1") (pin "1") (pinfunction "VIN_1") (pintype "power_in"))
      (node (ref "U2") (pin "1") (pinfunction "VIN_1") (pintype "power_in"))
    )
    (net (code "5") (name "12VRAW") (class "Default")
      (node (ref "C5") (pin "1") (pinfunction "1_1") (pintype "passive"))
      (node (ref "D3") (pin "A") (pinfunction "A_A") (pintype "passive"))
      (node (ref "JP1") (pin "2") (pinfunction "2_2") (pintype "passive"))
    )
    (net (code "6") (name "CAP_LINKS") (class "Default")
      (node (ref "C18") (pin "1") (pinfunction "1_1") (pintype "passive"))
      (node (ref "IC2") (pin "11") (pinfunction "3V3_OUT_11") (pintype "bidirectional"))
      (node (ref "IC2") (pin "20") (pinfunction "CAP2_20") (pintype "bidirectional"))
      (node (ref "IC2") (pin "3") (pinfunction "CAP1_3") (pintype "bidirectional"))
    )
    (net (code "7") (name "CM_USB_N") (class "Default")
      (node (ref "U$2") (pin "15") (pinfunction "DMU_15") (pintype "bidirectional"))
      (node (ref "U$3") (pin "5") (pinfunction "USB_N_5") (pintype "passive"))
    )
    (net (code "8") (name "CM_USB_P") (class "Default")
      (node (ref "U$2") (pin "16") (pinfunction "DPU_16") (pintype "bidirectional"))
      (node (ref "U$3") (pin "7") (pinfunction "USB_P_7") (pintype "passive"))
    )
    (net (code "9") (name "CT") (class "Default")
      (node (ref "C29") (pin "2") (pinfunction "2_2") (pintype "passive"))
      (node (ref "J2") (pin "7") (pinfunction "CT_7") (pintype "power_in"))
      (node (ref "R9") (pin "1") (pinfunction "1_1") (pintype "passive"))
    )
    (net (code "10") (name "ETH_DM") (class "Default")
      (node (ref "IC2") (pin "5") (pinfunction "USBD-_5") (pintype "bidirectional"))
      (node (ref "U$2") (pin "10") (pinfunction "DM1_10") (pintype "bidirectional"))
    )
    (net (code "11") (name "ETH_DP") (class "Default")
      (node (ref "IC2") (pin "6") (pinfunction "USBD+_6") (pintype "bidirectional"))
      (node (ref "U$2") (pin "11") (pinfunction "DP1_11") (pintype "bidirectional"))
    )
    (net (code "12") (name "GND") (class "Default")
      (node (ref "C1") (pin "2") (pinfunction "2_2") (pintype "passive"))
      (node (ref "C10") (pin "1") (pinfunction "1_1") (pintype "passive"))
      (node (ref "C11") (pin "1") (pinfunction "1_1") (pintype "passive"))
      (node (ref "C12") (pin "1") (pinfunction "1_1") (pintype "passive"))
      (node (ref "C13") (pin "1") (pinfunction "1_1") (pintype "passive"))
      (node (ref "C14") (pin "1") (pinfunction "1_1") (pintype "passive"))
      (node (ref "C15") (pin "1") (pinfunction "1_1") (pintype "passive"))
      (node (ref "C16") (pin "2") (pinfunction "2_2") (pintype "passive"))
      (node (ref "C17") (pin "2") (pinfunction "2_2") (pintype "passive"))
      (node (ref "C18") (pin "2") (pinfunction "2_2") (pintype "passive"))
      (node (ref "C19") (pin "2") (pinfunction "2_2") (pintype "passive"))
      (node (ref "C2") (pin "2") (pinfunction "2_2") (pintype "passive"))
      (node (ref "C20") (pin "2") (pinfunction "2_2") (pintype "passive"))
      (node (ref "C21") (pin "1") (pinfunction "1_1") (pintype "passive"))
      (node (ref "C22") (pin "1") (pinfunction "1_1") (pintype "passive"))
      (node (ref "C23") (pin "1") (pinfunction "1_1") (pintype "passive"))
      (node (ref "C29") (pin "1") (pinfunction "1_1") (pintype "passive"))
      (node (ref "C3") (pin "2") (pinfunction "2_2") (pintype "passive"))
      (node (ref "C31") (pin "-") (pinfunction "-_-") (pintype "passive"))
      (node (ref "C33") (pin "-") (pinfunction "-_-") (pintype "passive"))
      (node (ref "C34") (pin "-") (pinfunction "-_-") (pintype "passive"))
      (node (ref "C36") (pin "1") (pinfunction "1_1") (pintype "passive"))
      (node (ref "C37") (pin "2") (pinfunction "2_2") (pintype "passive"))
      (node (ref "C38") (pin "2") (pinfunction "2_2") (pintype "passive"))
      (node (ref "C39") (pin "2") (pinfunction "2_2") (pintype "passive"))
      (node (ref "C4") (pin "2") (pinfunction "2_2") (pintype "passive"))
      (node (ref "C5") (pin "2") (pinfunction "2_2") (pintype "passive"))
      (node (ref "C6") (pin "2") (pinfunction "2_2") (pintype "passive"))
      (node (ref "C7") (pin "-") (pinfunction "-_-") (pintype "passive"))
      (node (ref "C8") (pin "-") (pinfunction "-_-") (pintype "passive"))
      (node (ref "C9") (pin "1") (pinfunction "1_1") (pintype "passive"))
      (node (ref "D1") (pin "A") (pinfunction "A_A") (pintype "passive"))
      (node (ref "D2") (pin "A") (pinfunction "A_A") (pintype "passive"))
      (node (ref "IC1") (pin "1") (pinfunction "A0_1") (pintype "input"))
      (node (ref "IC1") (pin "2") (pinfunction "A1_2") (pintype "input"))
      (node (ref "IC1") (pin "3") (pinfunction "A2_3") (pintype "input"))
      (node (ref "IC1") (pin "4") (pinfunction "GND_4") (pintype "power_in"))
      (node (ref "IC1") (pin "7") (pinfunction "WP_7") (pintype "input"))
      (node (ref "IC2") (pin "12") (pinfunction "GND_2_12") (pintype "bidirectional"))
      (node (ref "IC2") (pin "21") (pinfunction "GND_3_21") (pintype "bidirectional"))
      (node (ref "IC2") (pin "22") (pinfunction "GND_4_22") (pintype "bidirectional"))
      (node (ref "IC2") (pin "28") (pinfunction "GND_5_28") (pintype "bidirectional"))
      (node (ref "IC2") (pin "33") (pinfunction "CNTR_PAD_33") (pintype "bidirectional"))
      (node (ref "IC2") (pin "4") (pinfunction "GND_1_4") (pintype "bidirectional"))
      (node (ref "IC3") (pin "1") (pinfunction "GND_1") (pintype "bidirectional"))
      (node (ref "J1") (pin "4") (pinfunction "4_4") (pintype "passive"))
      (node (ref "J1") (pin "5") (pinfunction "MNT_1_5") (pintype "passive"))
      (node (ref "J1") (pin "6") (pinfunction "MNT_2_6") (pintype "passive"))
      (node (ref "J3") (pin "C5") (pinfunction "GND_C5") (pintype "power_in"))
      (node (ref "J3") (pin "G1") (pinfunction "GND_G1") (pintype "power_in"))
      (node (ref "J3") (pin "G2") (pinfunction "GND_G2") (pintype "power_in"))
      (node (ref "J3") (pin "G3") (pinfunction "GND_G3") (pintype "power_in"))
      (node (ref "J3") (pin "G4") (pinfunction "GND_G4") (pintype "power_in"))
      (node (ref "J3") (pin "G5") (pinfunction "GND_G5") (pintype "power_in"))
      (node (ref "J3") (pin "G6") (pinfunction "GND_G6") (pintype "power_in"))
      (node (ref "R1") (pin "1") (pinfunction "1_1") (pintype "passive"))
      (node (ref "R19") (pin "1") (pinfunction "1_1") (pintype "passive"))
      (node (ref "R20") (pin "1") (pinfunction "1_1") (pintype "passive"))
      (node (ref "R23") (pin "2") (pinfunction "2_2") (pintype "passive"))
      (node (ref "R24") (pin "2") (pinfunction "2_2") (pintype "passive"))
      (node (ref "R5") (pin "1") (pinfunction "1_1") (pintype "passive"))
      (node (ref "R7") (pin "2") (pinfunction "2_2") (pintype "passive"))
      (node (ref "U$1") (pin "P$3") (pinfunction "-VDC_P$3") (pintype "bidirectional"))
      (node (ref "U$2") (pin "1") (pinfunction "VSS_1") (pintype "bidirectional"))
      (node (ref "U$3") (pin "3") (pinfunction "GND_3") (pintype "power_in"))
      (node (ref "U$3") (pin "4") (pinfunction "GND_4") (pintype "power_in"))
      (node (ref "U$3") (pin "59") (pinfunction "GND_59") (pintype "power_in"))
      (node (ref "U$3") (pin "60") (pinfunction "GND_60") (pintype "power_in"))
      (node (ref "U$4") (pin "10_GND") (pinfunction "10_GND_10_GND") (pintype "bidirectional"))
      (node (ref "U$4") (pin "12_GND") (pinfunction "12_GND_12_GND") (pintype "bidirectional"))
      (node (ref "U$4") (pin "13_GND") (pinfunction "13_GND_13_GND") (pintype "bidirectional"))
      (node (ref "U$4") (pin "24_GND") (pinfunction "24_GND_24_GND") (pintype "bidirectional"))
      (node (ref "U$5") (pin "14") (pinfunction "14-GND_14") (pintype "bidirectional"))
      (node (ref "U$5") (pin "20") (pinfunction "20-GND_20") (pintype "bidirectional"))
      (node (ref "U$5") (pin "25") (pinfunction "25-GND_25") (pintype "bidirectional"))
      (node (ref "U$5") (pin "30") (pinfunction "30-GND_30") (pintype "bidirectional"))
      (node (ref "U$5") (pin "34") (pinfunction "34-GND_34") (pintype "bidirectional"))
      (node (ref "U$5") (pin "39") (pinfunction "39-GND_39") (pintype "bidirectional"))
      (node (ref "U$5") (pin "6") (pinfunction "6-GND_6") (pintype "bidirectional"))
      (node (ref "U$5") (pin "9") (pinfunction "9-GND_9") (pintype "bidirectional"))
      (node (ref "U$8") (pin "GND") (pinfunction "RING_GND") (pintype "bidirectional"))
      (node (ref "U$8") (pin "GNDBREAK") (pinfunction "RING_SW_GNDBREAK") (pintype "bidirectional"))
      (node (ref "U1") (pin "4") (pinfunction "SD_4") (pintype "input"))
      (node (ref "U1") (pin "5") (pinfunction "GND1_5") (pintype "power_in"))
      (node (ref "U1") (pin "6") (pinfunction "GND2_6") (pintype "power_in"))
      (node (ref "U1") (pin "7") (pinfunction "GND3_7") (pintype "power_in"))
      (node (ref "U1") (pin "8") (pinfunction "GND4_8") (pintype "power_in"))
      (node (ref "U2") (pin "4") (pinfunction "SD_4") (pintype "input"))
      (node (ref "U2") (pin "5") (pinfunction "GND1_5") (pintype "power_in"))
      (node (ref "U2") (pin "6") (pinfunction "GND2_6") (pintype "power_in"))
      (node (ref "U2") (pin "7") (pinfunction "GND3_7") (pintype "power_in"))
      (node (ref "U2") (pin "8") (pinfunction "GND4_8") (pintype "power_in"))
      (node (ref "X1") (pin "15") (pinfunction "S_15") (pintype "passive"))
      (node (ref "X1") (pin "17") (pinfunction "S_17") (pintype "passive"))
      (node (ref "X1") (pin "18") (pinfunction "S_18") (pintype "passive"))
      (node (ref "X1") (pin "21") (pinfunction "S_21") (pintype "passive"))
      (node (ref "X1") (pin "26") (pinfunction "S_26") (pintype "passive"))
      (node (ref "X1") (pin "27") (pinfunction "S_27") (pintype "passive"))
      (node (ref "X1") (pin "29") (pinfunction "S_29") (pintype "passive"))
      (node (ref "X1") (pin "34") (pinfunction "S_34") (pintype "passive"))
      (node (ref "X1") (pin "35") (pinfunction "S_35") (pintype "passive"))
      (node (ref "X1") (pin "37") (pinfunction "S_37") (pintype "passive"))
      (node (ref "X1") (pin "4") (pinfunction "S_4") (pintype "passive"))
      (node (ref "X1") (pin "40") (pinfunction "S_40") (pintype "passive"))
      (node (ref "X1") (pin "43") (pinfunction "S_43") (pintype "passive"))
      (node (ref "X1") (pin "50") (pinfunction "S_50") (pintype "passive"))
      (node (ref "X1") (pin "9") (pinfunction "S_9") (pintype "passive"))
      (node (ref "X2") (pin "15") (pinfunction "S_15") (pintype "passive"))
      (node (ref "X2") (pin "17") (pinfunction "S_17") (pintype "passive"))
      (node (ref "X2") (pin "18") (pinfunction "S_18") (pintype "passive"))
      (node (ref "X2") (pin "21") (pinfunction "S_21") (pintype "passive"))
      (node (ref "X2") (pin "26") (pinfunction "S_26") (pintype "passive"))
      (node (ref "X2") (pin "27") (pinfunction "S_27") (pintype "passive"))
      (node (ref "X2") (pin "29") (pinfunction "S_29") (pintype "passive"))
      (node (ref "X2") (pin "34") (pinfunction "S_34") (pintype "passive"))
      (node (ref "X2") (pin "35") (pinfunction "S_35") (pintype "passive"))
      (node (ref "X2") (pin "37") (pinfunction "S_37") (pintype "passive"))
      (node (ref "X2") (pin "4") (pinfunction "S_4") (pintype "passive"))
      (node (ref "X2") (pin "40") (pinfunction "S_40") (pintype "passive"))
      (node (ref "X2") (pin "43") (pinfunction "S_43") (pintype "passive"))
      (node (ref "X2") (pin "50") (pinfunction "S_50") (pintype "passive"))
      (node (ref "X2") (pin "9") (pinfunction "S_9") (pintype "passive"))
      (node (ref "X3") (pin "15") (pinfunction "S_15") (pintype "passive"))
      (node (ref "X3") (pin "17") (pinfunction "S_17") (pintype "passive"))
      (node (ref "X3") (pin "18") (pinfunction "S_18") (pintype "passive"))
      (node (ref "X3") (pin "21") (pinfunction "S_21") (pintype "passive"))
      (node (ref "X3") (pin "26") (pinfunction "S_26") (pintype "passive"))
      (node (ref "X3") (pin "27") (pinfunction "S_27") (pintype "passive"))
      (node (ref "X3") (pin "29") (pinfunction "S_29") (pintype "passive"))
      (node (ref "X3") (pin "34") (pinfunction "S_34") (pintype "passive"))
      (node (ref "X3") (pin "35") (pinfunction "S_35") (pintype "passive"))
      (node (ref "X3") (pin "37") (pinfunction "S_37") (pintype "passive"))
      (node (ref "X3") (pin "4") (pinfunction "S_4") (pintype "passive"))
      (node (ref "X3") (pin "40") (pinfunction "S_40") (pintype "passive"))
      (node (ref "X3") (pin "43") (pinfunction "S_43") (pintype "passive"))
      (node (ref "X3") (pin "50") (pinfunction "S_50") (pintype "passive"))
      (node (ref "X3") (pin "9") (pinfunction "S_9") (pintype "passive"))
      (node (ref "X4") (pin "1") (pinfunction "GND_1") (pintype "passive"))
      (node (ref "X4") (pin "2") (pinfunction "GND_2") (pintype "passive"))
    )
    (net (code "13") (name "GPIO_0") (class "Default")
      (node (ref "U$3") (pin "58") (pinfunction "GPIO0_58") (pintype "passive"))
    )
    (net (code "14") (name "GPIO_1") (class "Default")
      (node (ref "U$3") (pin "57") (pinfunction "GPIO1_57") (pintype "passive"))
    )
    (net (code "15") (name "GPIO_4") (class "Default")
      (node (ref "U$3") (pin "54") (pinfunction "GPIO4_54") (pintype "passive"))
      (node (ref "U$5") (pin "7") (pinfunction "7-GPIO4_7") (pintype "bidirectional"))
    )
    (net (code "16") (name "GPIO_5") (class "Default")
      (node (ref "U$3") (pin "53") (pinfunction "GPIO5_53") (pintype "passive"))
    )
    (net (code "17") (name "GPIO_6") (class "Default")
      (node (ref "U$3") (pin "52") (pinfunction "GPIO6_52") (pintype "passive"))
    )
    (net (code "18") (name "GPIO_7") (class "Default")
      (node (ref "U$5") (pin "26") (pinfunction "26-GPIO7_26") (pintype "bidirectional"))
    )
    (net (code "19") (name "GPIO_8") (class "Default")
      (node (ref "U$3") (pin "50") (pinfunction "GPIO8_50") (pintype "passive"))
      (node (ref "U$5") (pin "24") (pinfunction "24-GPIO8_24") (pintype "bidirectional"))
    )
    (net (code "20") (name "GPIO_9") (class "Default")
      (node (ref "U$3") (pin "48") (pinfunction "GPIO9_48") (pintype "passive"))
      (node (ref "U$5") (pin "21") (pinfunction "21-SPI-MISO/GPIO9_21") (pintype "bidirectional"))
    )
    (net (code "21") (name "GPIO_10") (class "Default")
      (node (ref "U$3") (pin "46") (pinfunction "GPIO10_46") (pintype "passive"))
      (node (ref "U$5") (pin "19") (pinfunction "19-SPI-MOSI/GPIO10_19") (pintype "bidirectional"))
    )
    (net (code "22") (name "GPIO_11") (class "Default")
      (node (ref "U$3") (pin "44") (pinfunction "GPIO11_44") (pintype "passive"))
      (node (ref "U$5") (pin "23") (pinfunction "23-SPI-SCLK/GPIO11_23") (pintype "bidirectional"))
    )
    (net (code "23") (name "GPIO_12") (class "Default")
      (node (ref "U$3") (pin "42") (pinfunction "GPIO12_42") (pintype "passive"))
    )
    (net (code "24") (name "GPIO_13") (class "Default")
      (node (ref "U$3") (pin "40") (pinfunction "GPIO13_40") (pintype "passive"))
    )
    (net (code "25") (name "GPIO_14") (class "Default")
      (node (ref "U$3") (pin "38") (pinfunction "GPIO14_38") (pintype "passive"))
      (node (ref "U$5") (pin "8") (pinfunction "8-TX_8") (pintype "bidirectional"))
    )
    (net (code "26") (name "GPIO_15") (class "Default")
      (node (ref "U$3") (pin "36") (pinfunction "GPIO15_36") (pintype "passive"))
      (node (ref "U$5") (pin "10") (pinfunction "10-RX_10") (pintype "bidirectional"))
    )
    (net (code "27") (name "GPIO_17") (class "Default")
      (node (ref "U$3") (pin "32") (pinfunction "GPIO17_32") (pintype "passive"))
      (node (ref "U$5") (pin "11") (pinfunction "11-GPIO17_11") (pintype "bidirectional"))
    )
    (net (code "28") (name "GPIO_18") (class "Default")
      (node (ref "U$3") (pin "30") (pinfunction "GPIO18_30") (pintype "passive"))
      (node (ref "U$5") (pin "12") (pinfunction "12-GPIO18_12") (pintype "bidirectional"))
    )
    (net (code "29") (name "GPIO_22") (class "Default")
      (node (ref "U$3") (pin "22") (pinfunction "GPIO22_22") (pintype "passive"))
      (node (ref "U$5") (pin "15") (pinfunction "15-GPIO22_15") (pintype "bidirectional"))
    )
    (net (code "30") (name "GPIO_23") (class "Default")
      (node (ref "U$3") (pin "20") (pinfunction "GPIO23_20") (pintype "passive"))
      (node (ref "U$5") (pin "16") (pinfunction "16-GPIO23_16") (pintype "bidirectional"))
    )
    (net (code "31") (name "GPIO_24") (class "Default")
      (node (ref "U$3") (pin "18") (pinfunction "GPIO24_18") (pintype "passive"))
      (node (ref "U$5") (pin "18") (pinfunction "18-GPIO24_18") (pintype "bidirectional"))
    )
    (net (code "32") (name "GPIO_25") (class "Default")
      (node (ref "U$3") (pin "16") (pinfunction "GPIO25_16") (pintype "passive"))
      (node (ref "U$5") (pin "22") (pinfunction "22-GPIO25_22") (pintype "bidirectional"))
    )
    (net (code "33") (name "GPIO_26") (class "Default")
      (node (ref "U$3") (pin "14") (pinfunction "GPIO26_14") (pintype "passive"))
    )
    (net (code "34") (name "GPIO_27") (class "Default")
      (node (ref "U$3") (pin "13") (pinfunction "GPIO27_13") (pintype "passive"))
      (node (ref "U$5") (pin "13") (pinfunction "13-GPIO27_13") (pintype "bidirectional"))
    )
    (net (code "35") (name "GPS_PPS") (class "Default")
      (node (ref "U$4") (pin "3_TIMEPULSE") (pinfunction "3_TIMEPULSE_3_TIMEPULSE") (pintype "bidirectional"))
      (node (ref "X1") (pin "19") (pinfunction "S_19") (pintype "passive"))
      (node (ref "X3") (pin "19") (pinfunction "S_19") (pintype "passive"))
    )
    (net (code "36") (name "GPS_RX") (class "Default")
      (node (ref "U$3") (pin "39") (pinfunction "GPIO33_39") (pintype "passive"))
      (node (ref "U$4") (pin "20_TXD1") (pinfunction "20_TXD1_20_TXD1") (pintype "bidirectional"))
    )
    (net (code "37") (name "GPS_SCL") (class "Default")
      (node (ref "IC1") (pin "6") (pinfunction "SCL_6") (pintype "input"))
      (node (ref "U$4") (pin "19_SCL2") (pinfunction "19_SCL2_19_SCL2") (pintype "bidirectional"))
    )
    (net (code "38") (name "GPS_SDA") (class "Default")
      (node (ref "IC1") (pin "5") (pinfunction "SDA_5") (pintype "bidirectional"))
      (node (ref "U$4") (pin "18_SDA2") (pinfunction "18_SDA2_18_SDA2") (pintype "bidirectional"))
    )
    (net (code "39") (name "GPS_TX") (class "Default")
      (node (ref "U$3") (pin "41") (pinfunction "GPIO32_41") (pintype "passive"))
      (node (ref "U$4") (pin "21_RXD1") (pinfunction "21_RXD1_21_RXD1") (pintype "bidirectional"))
    )
    (net (code "40") (name "I2C1_SCL") (class "Default")
      (node (ref "U$3") (pin "55") (pinfunction "GPIO3_55") (pintype "passive"))
      (node (ref "U$5") (pin "5") (pinfunction "5-SCL1/GPIO3_5") (pintype "bidirectional"))
      (node (ref "X2") (pin "30") (pinfunction "S_30") (pintype "passive"))
    )
    (net (code "41") (name "I2C1_SDA") (class "Default")
      (node (ref "U$3") (pin "56") (pinfunction "GPIO2_56") (pintype "passive"))
      (node (ref "U$5") (pin "3") (pinfunction "3-SDA1/GPIO2_3") (pintype "bidirectional"))
      (node (ref "X2") (pin "32") (pinfunction "S_32") (pintype "passive"))
    )
    (net (code "42") (name "LED1-") (class "Default")
      (node (ref "J2") (pin "12") (pinfunction "1_LED1_12") (pintype "passive"))
      (node (ref "R21") (pin "2") (pinfunction "2_2") (pintype "passive"))
    )
    (net (code "43") (name "LED2-") (class "Default")
      (node (ref "J2") (pin "14") (pinfunction "LED2_CATHODE_14") (pintype "passive"))
      (node (ref "R12") (pin "1") (pinfunction "1_1") (pintype "passive"))
    )
    (net (code "44") (name "LORA_RS1") (class "Default")
      (node (ref "U$3") (pin "29") (pinfunction "GPIO38_29") (pintype "passive"))
      (node (ref "X1") (pin "22") (pinfunction "S_22") (pintype "passive"))
    )
    (net (code "45") (name "LORA_RS2") (class "Default")
      (node (ref "U$3") (pin "27") (pinfunction "GPIO39_27") (pintype "passive"))
      (node (ref "X3") (pin "22") (pinfunction "S_22") (pintype "passive"))
    )
    (net (code "46") (name "Net-(D4-PadC)") (class "Default")
      (node (ref "D4") (pin "C") (pinfunction "C_C") (pintype "passive"))
      (node (ref "R19") (pin "2") (pinfunction "2_2") (pintype "passive"))
    )
    (net (code "47") (name "Net-(D5-PadC)") (class "Default")
      (node (ref "D5") (pin "C") (pinfunction "C_C") (pintype "passive"))
      (node (ref "R20") (pin "2") (pinfunction "2_2") (pintype "passive"))
    )
    (net (code "48") (name "Net-(D6-PadC)") (class "Default")
      (node (ref "D6") (pin "C") (pinfunction "C_C") (pintype "passive"))
      (node (ref "R5") (pin "2") (pinfunction "2_2") (pintype "passive"))
    )
    (net (code "49") (name "Net-(D7-A)") (class "Default")
      (node (ref "B1") (pin "-") (pinfunction "-_-") (pintype "passive"))
      (node (ref "B2") (pin "-") (pinfunction "-_-") (pintype "passive"))
      (node (ref "D7") (pin "P$2") (pinfunction "A_P$2") (pintype "passive"))
      (node (ref "U$1") (pin "P$7") (pinfunction "VIN-_P$7") (pintype "bidirectional"))
      (node (ref "U$1") (pin "P$8") (pinfunction "VIN-_P$8") (pintype "bidirectional"))
    )
    (net (code "50") (name "Net-(D7-C)") (class "Default")
      (node (ref "B1") (pin "+") (pinfunction "+_+") (pintype "passive"))
      (node (ref "B2") (pin "+") (pinfunction "+_+") (pintype "passive"))
      (node (ref "D7") (pin "P$1") (pinfunction "C_P$1") (pintype "passive"))
      (node (ref "U$1") (pin "P$5") (pinfunction "VIN+_P$5") (pintype "bidirectional"))
      (node (ref "U$1") (pin "P$6") (pinfunction "VIN+_P$6") (pintype "bidirectional"))
    )
    (net (code "51") (name "Net-(IC2-ETH_LINK)") (class "Default")
      (node (ref "IC2") (pin "19") (pinfunction "ETH_LINK_19") (pintype "bidirectional"))
      (node (ref "R21") (pin "1") (pinfunction "1_1") (pintype "passive"))
    )
    (net (code "52") (name "Net-(IC2-ETH_SPD)") (class "Default")
      (node (ref "IC2") (pin "8") (pinfunction "ETH_SPD_8") (pintype "bidirectional"))
      (node (ref "R12") (pin "2") (pinfunction "2_2") (pintype "passive"))
    )
    (net (code "53") (name "Net-(IC2-REXT)") (class "Default")
      (node (ref "IC2") (pin "2") (pinfunction "REXT_2") (pintype "bidirectional"))
      (node (ref "R24") (pin "1") (pinfunction "1_1") (pintype "passive"))
    )
    (net (code "54") (name "Net-(IC2-VBUS_SENSE)") (class "Default")
      (node (ref "C21") (pin "2") (pinfunction "2_2") (pintype "passive"))
      (node (ref "IC2") (pin "1") (pinfunction "VBUS_SENSE_1") (pintype "bidirectional"))
      (node (ref "R22") (pin "1") (pinfunction "1_1") (pintype "passive"))
      (node (ref "R23") (pin "1") (pinfunction "1_1") (pintype "passive"))
    )
    (net (code "55") (name "Net-(IC2-XTALIN)") (class "Default")
      (node (ref "C23") (pin "2") (pinfunction "2_2") (pintype "passive"))
      (node (ref "IC2") (pin "10") (pinfunction "XTALIN_10") (pintype "bidirectional"))
      (node (ref "R25") (pin "1") (pinfunction "1_1") (pintype "passive"))
      (node (ref "Y3") (pin "1") (pinfunction "1_1") (pintype "passive"))
    )
    (net (code "56") (name "Net-(IC2-XTALOUT)") (class "Default")
      (node (ref "C22") (pin "2") (pinfunction "2_2") (pintype "passive"))
      (node (ref "IC2") (pin "9") (pinfunction "XTALOUT_9") (pintype "bidirectional"))
      (node (ref "R25") (pin "2") (pinfunction "2_2") (pintype "passive"))
      (node (ref "Y3") (pin "2") (pinfunction "2_2") (pintype "passive"))
    )
    (net (code "57") (name "Net-(J2-1_GND)") (class "Default")
      (node (ref "J2") (pin "16") (pinfunction "1_GND_16") (pintype "passive"))
      (node (ref "J2") (pin "17") (pinfunction "2_GND_17") (pintype "passive"))
    )
    (net (code "58") (name "Net-(J3-CLK)") (class "Default")
      (node (ref "J3") (pin "C3") (pinfunction "CLK_C3") (pintype "input"))
      (node (ref "R16") (pin "2") (pinfunction "2_2") (pintype "passive"))
    )
    (net (code "59") (name "Net-(J3-I{slash}O)") (class "Default")
      (node (ref "J3") (pin "C7") (pinfunction "I/O_C7") (pintype "bidirectional"))
      (node (ref "R17") (pin "1") (pinfunction "1_1") (pintype "passive"))
    )
    (net (code "60") (name "Net-(J3-RST)") (class "Default")
      (node (ref "J3") (pin "C2") (pinfunction "RST_C2") (pintype "input"))
      (node (ref "R15") (pin "2") (pinfunction "2_2") (pintype "passive"))
    )
    (net (code "61") (name "Net-(JP1-Pad1)") (class "Default")
      (node (ref "JP1") (pin "1") (pinfunction "1_1") (pintype "passive"))
      (node (ref "U$1") (pin "P$1") (pinfunction "+VDC_P$1") (pintype "bidirectional"))
      (node (ref "U$1") (pin "P$2") (pinfunction "+VDC_P$2") (pintype "bidirectional"))
    )
    (net (code "62") (name "Net-(L3-Pad1)") (class "Default")
      (node (ref "L3") (pin "1") (pinfunction "1_1") (pintype "passive"))
      (node (ref "U$4") (pin "8_RESERVED") (pinfunction "8_RESERVED_8_RESERVED") (pintype "bidirectional"))
      (node (ref "U$4") (pin "9_VCC_RF") (pinfunction "9_VCC_RF_9_VCC_RF") (pintype "bidirectional"))
    )
    (net (code "63") (name "Net-(L3-Pad2)") (class "Default")
      (node (ref "L3") (pin "2") (pinfunction "2_2") (pintype "passive"))
      (node (ref "R8") (pin "1") (pinfunction "1_1") (pintype "passive"))
    )
    (net (code "64") (name "Net-(LED1-PadA)") (class "Default")
      (node (ref "LED1") (pin "A") (pinfunction "A_A") (pintype "passive"))
      (node (ref "R10") (pin "1") (pinfunction "1_1") (pintype "passive"))
    )
    (net (code "65") (name "Net-(LED1-PadC)") (class "Default")
      (node (ref "LED1") (pin "C") (pinfunction "C_C") (pintype "passive"))
      (node (ref "U$4") (pin "22_V_BCKP") (pinfunction "22_V_BCKP_22_V_BCKP") (pintype "bidirectional"))
    )
    (net (code "66") (name "Net-(U$2-BUSJ)") (class "Default")
      (node (ref "R3") (pin "2") (pinfunction "2_2") (pintype "passive"))
      (node (ref "U$2") (pin "19") (pinfunction "BUSJ_19") (pintype "bidirectional"))
    )
    (net (code "67") (name "Net-(U$2-OVCJ)") (class "Default")
      (node (ref "R4") (pin "2") (pinfunction "2_2") (pintype "passive"))
      (node (ref "U$2") (pin "26") (pinfunction "OVCJ_26") (pintype "bidirectional"))
    )
    (net (code "68") (name "Net-(U$2-REXT)") (class "Default")
      (node (ref "R1") (pin "2") (pinfunction "2_2") (pintype "passive"))
      (node (ref "U$2") (pin "14") (pinfunction "REXT_14") (pintype "bidirectional"))
    )
    (net (code "69") (name "Net-(U$2-VBUSM)") (class "Default")
      (node (ref "R6") (pin "1") (pinfunction "1_1") (pintype "passive"))
      (node (ref "R7") (pin "1") (pinfunction "1_1") (pintype "passive"))
      (node (ref "U$2") (pin "18") (pinfunction "VBUSM_18") (pintype "bidirectional"))
    )
    (net (code "70") (name "Net-(U$2-VD18)") (class "Default")
      (node (ref "C14") (pin "2") (pinfunction "2_2") (pintype "passive"))
      (node (ref "C15") (pin "2") (pinfunction "2_2") (pintype "passive"))
      (node (ref "U$2") (pin "12") (pinfunction "VD18_O_12") (pintype "bidirectional"))
      (node (ref "U$2") (pin "28") (pinfunction "VD18_28") (pintype "bidirectional"))
    )
    (net (code "71") (name "Net-(U$2-VD33)") (class "Default")
      (node (ref "C12") (pin "2") (pinfunction "2_2") (pintype "passive"))
      (node (ref "C13") (pin "2") (pinfunction "2_2") (pintype "passive"))
      (node (ref "U$2") (pin "13") (pinfunction "VD33_13") (pintype "bidirectional"))
      (node (ref "U$2") (pin "21") (pinfunction "VD33_O_21") (pintype "bidirectional"))
    )
    (net (code "72") (name "Net-(U$2-XIN)") (class "Default")
      (node (ref "U$2") (pin "3") (pinfunction "XIN_3") (pintype "bidirectional"))
      (node (ref "Y2") (pin "1") (pinfunction "1_1") (pintype "passive"))
    )
    (net (code "73") (name "Net-(U$2-XOUT)") (class "Default")
      (node (ref "U$2") (pin "2") (pinfunction "XOUT_2") (pintype "bidirectional"))
      (node (ref "Y2") (pin "2") (pinfunction "2_2") (pintype "passive"))
    )
    (net (code "74") (name "Net-(U$2-XRSTJ)") (class "Default")
      (node (ref "R2") (pin "2") (pinfunction "2_2") (pintype "passive"))
      (node (ref "U$2") (pin "17") (pinfunction "XRSTJ_17") (pintype "bidirectional"))
    )
    (net (code "75") (name "Net-(U$8-TIP)") (class "Default")
      (node (ref "JP1") (pin "3") (pinfunction "3_3") (pintype "passive"))
      (node (ref "U$8") (pin "PWR2") (pinfunction "TIP_PWR2") (pintype "bidirectional"))
    )
    (net (code "76") (name "Net-(U1-OUT)") (class "Default")
      (node (ref "D2") (pin "C") (pinfunction "C_C") (pintype "passive"))
      (node (ref "L2") (pin "1") (pinfunction "1_1") (pintype "bidirectional"))
      (node (ref "U1") (pin "2") (pinfunction "OUT_2") (pintype "output"))
    )
    (net (code "77") (name "Net-(U2-OUT)") (class "Default")
      (node (ref "D1") (pin "C") (pinfunction "C_C") (pintype "passive"))
      (node (ref "L1") (pin "1") (pinfunction "1_1") (pintype "bidirectional"))
      (node (ref "U2") (pin "2") (pinfunction "OUT_2") (pintype "output"))
    )
    (net (code "78") (name "Net-(X4-SIGNAL)") (class "Default")
      (node (ref "R8") (pin "2") (pinfunction "2_2") (pintype "passive"))
      (node (ref "U$4") (pin "11_RF_IN") (pinfunction "11_RF_IN_11_RF_IN") (pintype "bidirectional"))
      (node (ref "X4") (pin "3") (pinfunction "SIGNAL_3") (pintype "passive"))
    )
    (net (code "79") (name "RD+") (class "Default")
      (node (ref "IC2") (pin "15") (pinfunction "ETH_RX+_15") (pintype "bidirectional"))
      (node (ref "J2") (pin "1") (pinfunction "RD+_1") (pintype "input"))
    )
    (net (code "80") (name "RD-") (class "Default")
      (node (ref "IC2") (pin "16") (pinfunction "ETH_RX-_16") (pintype "bidirectional"))
      (node (ref "J2") (pin "8") (pinfunction "RD-_8") (pintype "input"))
    )
    (net (code "81") (name "SIM_CLK") (class "Default")
      (node (ref "R16") (pin "1") (pinfunction "1_1") (pintype "passive"))
      (node (ref "X2") (pin "12") (pinfunction "S_12") (pintype "passive"))
    )
    (net (code "82") (name "SIM_DATA") (class "Default")
      (node (ref "R17") (pin "2") (pinfunction "2_2") (pintype "passive"))
      (node (ref "R18") (pin "2") (pinfunction "2_2") (pintype "passive"))
      (node (ref "X2") (pin "10") (pinfunction "S_10") (pintype "passive"))
    )
    (net (code "83") (name "SIM_RST") (class "Default")
      (node (ref "R15") (pin "1") (pinfunction "1_1") (pintype "passive"))
      (node (ref "X2") (pin "14") (pinfunction "S_14") (pintype "passive"))
    )
    (net (code "84") (name "SIM_VCC") (class "Default")
      (node (ref "C37") (pin "1") (pinfunction "1_1") (pintype "passive"))
      (node (ref "J3") (pin "C1") (pinfunction "VCC_C1") (pintype "power_in"))
      (node (ref "R18") (pin "1") (pinfunction "1_1") (pintype "passive"))
      (node (ref "X2") (pin "8") (pinfunction "S_8") (pintype "passive"))
    )
    (net (code "85") (name "SPI0_CE1") (class "Default")
      (node (ref "U$3") (pin "51") (pinfunction "GPIO7_51") (pintype "passive"))
    )
    (net (code "86") (name "SPI1_CE2") (class "Default")
      (node (ref "U$3") (pin "34") (pinfunction "GPIO16_34") (pintype "passive"))
      (node (ref "X1") (pin "51") (pinfunction "S_51") (pintype "passive"))
    )
    (net (code "87") (name "SPI1_MISO") (class "Default")
      (node (ref "U$3") (pin "28") (pinfunction "GPIO19_28") (pintype "passive"))
      (node (ref "X1") (pin "47") (pinfunction "S_47") (pintype "passive"))
    )
    (net (code "88") (name "SPI1_MOSI") (class "Default")
      (node (ref "U$3") (pin "26") (pinfunction "GPIO20_26") (pintype "passive"))
      (node (ref "X1") (pin "49") (pinfunction "S_49") (pintype "passive"))
    )
    (net (code "89") (name "SPI1_SCLK") (class "Default")
      (node (ref "U$3") (pin "24") (pinfunction "GPIO21_24") (pintype "passive"))
      (node (ref "X1") (pin "45") (pinfunction "S_45") (pintype "passive"))
    )
    (net (code "90") (name "SPI2_CE0") (class "Default")
      (node (ref "U$3") (pin "19") (pinfunction "GPIO43_19") (pintype "passive"))
      (node (ref "X3") (pin "51") (pinfunction "S_51") (pintype "passive"))
    )
    (net (code "91") (name "SPI2_MISO") (class "Default")
      (node (ref "U$3") (pin "25") (pinfunction "GPIO40_25") (pintype "passive"))
      (node (ref "X3") (pin "47") (pinfunction "S_47") (pintype "passive"))
    )
    (net (code "92") (name "SPI2_MOSI") (class "Default")
      (node (ref "U$3") (pin "23") (pinfunction "GPIO41_23") (pintype "passive"))
      (node (ref "X3") (pin "49") (pinfunction "S_49") (pintype "passive"))
    )
    (net (code "93") (name "SPI2_SCLK") (class "Default")
      (node (ref "U$3") (pin "21") (pinfunction "GPIO42_21") (pintype "passive"))
      (node (ref "X3") (pin "45") (pinfunction "S_45") (pintype "passive"))
    )
    (net (code "94") (name "TD+") (class "Default")
      (node (ref "IC2") (pin "14") (pinfunction "ETH_TX+_14") (pintype "bidirectional"))
      (node (ref "J2") (pin "2") (pinfunction "TD+_2") (pintype "output"))
    )
    (net (code "95") (name "TD-") (class "Default")
      (node (ref "IC2") (pin "13") (pinfunction "ETH_TX-_13") (pintype "bidirectional"))
      (node (ref "J2") (pin "9") (pinfunction "TD-_9") (pintype "output"))
    )
    (net (code "96") (name "USB1+") (class "Default")
      (node (ref "U$2") (pin "9") (pinfunction "DP2_9") (pintype "bidirectional"))
      (node (ref "X2") (pin "38") (pinfunction "S_38") (pintype "passive"))
    )
    (net (code "97") (name "USB1-") (class "Default")
      (node (ref "U$2") (pin "8") (pinfunction "DM2_8") (pintype "bidirectional"))
      (node (ref "X2") (pin "36") (pinfunction "S_36") (pintype "passive"))
    )
    (net (code "98") (name "USB2+") (class "Default")
      (node (ref "J1") (pin "3") (pinfunction "3_3") (pintype "passive"))
      (node (ref "U$2") (pin "7") (pinfunction "DP3_7") (pintype "bidirectional"))
    )
    (net (code "99") (name "USB2-") (class "Default")
      (node (ref "J1") (pin "2") (pinfunction "2_2") (pintype "passive"))
      (node (ref "U$2") (pin "6") (pinfunction "DM3_6") (pintype "bidirectional"))
    )
    (net (code "100") (name "VC12") (class "Default")
      (node (ref "B1") (pin "~1") (pinfunction "AC1_~1") (pintype "passive"))
      (node (ref "J2") (pin "5") (pinfunction "VC12_5") (pintype "power_in"))
    )
    (net (code "101") (name "VC36") (class "Default")
      (node (ref "B2") (pin "~1") (pinfunction "AC1_~1") (pintype "passive"))
      (node (ref "J2") (pin "10") (pinfunction "VC36_10") (pintype "power_in"))
    )
    (net (code "102") (name "VC45") (class "Default")
      (node (ref "B1") (pin "~2") (pinfunction "AC2_~2") (pintype "passive"))
      (node (ref "J2") (pin "6") (pinfunction "VC45_6") (pintype "power_in"))
    )
    (net (code "103") (name "VC78") (class "Default")
      (node (ref "B2") (pin "~2") (pinfunction "AC2_~2") (pintype "passive"))
      (node (ref "J2") (pin "11") (pinfunction "VC78_11") (pintype "power_in"))
    )
    (net (code "104") (name "VPP") (class "Default")
      (node (ref "J3") (pin "C6") (pinfunction "VPP_C6") (pintype "power_in"))
    )
    (net (code "105") (name "unconnected-(IC2-E0-Pad17)") (class "Default")
      (node (ref "IC2") (pin "17") (pinfunction "E0_17") (pintype "bidirectional"))
    )
    (net (code "106") (name "unconnected-(IC2-E1-Pad18)") (class "Default")
      (node (ref "IC2") (pin "18") (pinfunction "E1_18") (pintype "bidirectional"))
    )
    (net (code "107") (name "unconnected-(IC2-E2-Pad29)") (class "Default")
      (node (ref "IC2") (pin "29") (pinfunction "E2_29") (pintype "bidirectional"))
    )
    (net (code "108") (name "unconnected-(IC2-E3-Pad30)") (class "Default")
      (node (ref "IC2") (pin "30") (pinfunction "E3_30") (pintype "bidirectional"))
    )
    (net (code "109") (name "unconnected-(IC2-E4-Pad26)") (class "Default")
      (node (ref "IC2") (pin "26") (pinfunction "E4_26") (pintype "bidirectional"))
    )
    (net (code "110") (name "unconnected-(IC2-E5-Pad25)") (class "Default")
      (node (ref "IC2") (pin "25") (pinfunction "E5_25") (pintype "bidirectional"))
    )
    (net (code "111") (name "unconnected-(IC2-E6-Pad23)") (class "Default")
      (node (ref "IC2") (pin "23") (pinfunction "E6_23") (pintype "bidirectional"))
    )
    (net (code "112") (name "unconnected-(IC2-E7-Pad24)") (class "Default")
      (node (ref "IC2") (pin "24") (pinfunction "E7_24") (pintype "bidirectional"))
    )
    (net (code "113") (name "unconnected-(IC2-LOW_PWR#-Pad27)") (class "Default")
      (node (ref "IC2") (pin "27") (pinfunction "LOW_PWR#_27") (pintype "bidirectional"))
    )
    (net (code "114") (name "unconnected-(IC2-SCL-Pad31)") (class "Default")
      (node (ref "IC2") (pin "31") (pinfunction "SCL_31") (pintype "bidirectional"))
    )
    (net (code "115") (name "unconnected-(IC2-SDA-Pad32)") (class "Default")
      (node (ref "IC2") (pin "32") (pinfunction "SDA_32") (pintype "bidirectional"))
    )
    (net (code "116") (name "unconnected-(U$1-ADJ-PadP$4)") (class "Default")
      (node (ref "U$1") (pin "P$4") (pinfunction "ADJ_P$4") (pintype "bidirectional"))
    )
    (net (code "117") (name "unconnected-(U$2-DM4-Pad4)") (class "Default")
      (node (ref "U$2") (pin "4") (pinfunction "DM4_4") (pintype "bidirectional"))
    )
    (net (code "118") (name "unconnected-(U$2-DP4-Pad5)") (class "Default")
      (node (ref "U$2") (pin "5") (pinfunction "DP4_5") (pintype "bidirectional"))
    )
    (net (code "119") (name "unconnected-(U$2-DRV-Pad22)") (class "Default")
      (node (ref "U$2") (pin "22") (pinfunction "DRV_22") (pintype "bidirectional"))
    )
    (net (code "120") (name "unconnected-(U$2-LED1-Pad23)") (class "Default")
      (node (ref "U$2") (pin "23") (pinfunction "LED1_23") (pintype "bidirectional"))
    )
    (net (code "121") (name "unconnected-(U$2-LED2-Pad24)") (class "Default")
      (node (ref "U$2") (pin "24") (pinfunction "LED2_24") (pintype "bidirectional"))
    )
    (net (code "122") (name "unconnected-(U$2-PWRJ-Pad25)") (class "Default")
      (node (ref "U$2") (pin "25") (pinfunction "PWRJ_25") (pintype "bidirectional"))
    )
    (net (code "123") (name "unconnected-(U$2-TESTJ-Pad27)") (class "Default")
      (node (ref "U$2") (pin "27") (pinfunction "TESTJ_27") (pintype "bidirectional"))
    )
    (net (code "124") (name "unconnected-(U$3-GPIO28-Pad49)") (class "Default")
      (node (ref "U$3") (pin "49") (pinfunction "GPIO28_49") (pintype "passive"))
    )
    (net (code "125") (name "unconnected-(U$3-GPIO29-Pad47)") (class "Default")
      (node (ref "U$3") (pin "47") (pinfunction "GPIO29_47") (pintype "passive"))
    )
    (net (code "126") (name "unconnected-(U$3-GPIO30-Pad45)") (class "Default")
      (node (ref "U$3") (pin "45") (pinfunction "GPIO30_45") (pintype "passive"))
    )
    (net (code "127") (name "unconnected-(U$3-GPIO31-Pad43)") (class "Default")
      (node (ref "U$3") (pin "43") (pinfunction "GPIO31_43") (pintype "passive"))
    )
    (net (code "128") (name "unconnected-(U$3-GPIO34-Pad37)") (class "Default")
      (node (ref "U$3") (pin "37") (pinfunction "GPIO34_37") (pintype "passive"))
    )
    (net (code "129") (name "unconnected-(U$3-GPIO35-Pad35)") (class "Default")
      (node (ref "U$3") (pin "35") (pinfunction "GPIO35_35") (pintype "passive"))
    )
    (net (code "130") (name "unconnected-(U$3-GPIO36-Pad33)") (class "Default")
      (node (ref "U$3") (pin "33") (pinfunction "GPIO36_33") (pintype "passive"))
    )
    (net (code "131") (name "unconnected-(U$3-GPIO37-Pad31)") (class "Default")
      (node (ref "U$3") (pin "31") (pinfunction "GPIO37_31") (pintype "passive"))
    )
    (net (code "132") (name "unconnected-(U$3-GPIO44-Pad17)") (class "Default")
      (node (ref "U$3") (pin "17") (pinfunction "GPIO44_17") (pintype "passive"))
    )
    (net (code "133") (name "unconnected-(U$3-GPIO45-Pad15)") (class "Default")
      (node (ref "U$3") (pin "15") (pinfunction "GPIO45_15") (pintype "passive"))
    )
    (net (code "134") (name "unconnected-(U$3-Pad6)") (class "Default")
      (node (ref "U$3") (pin "6") (pinfunction "6_6") (pintype "passive"))
    )
    (net (code "135") (name "unconnected-(U$3-Pad8)") (class "Default")
      (node (ref "U$3") (pin "8") (pinfunction "8_8") (pintype "passive"))
    )
    (net (code "136") (name "unconnected-(U$3-Pad9)") (class "Default")
      (node (ref "U$3") (pin "9") (pinfunction "9_9") (pintype "passive"))
    )
    (net (code "137") (name "unconnected-(U$3-Pad10)") (class "Default")
      (node (ref "U$3") (pin "10") (pinfunction "10_10") (pintype "passive"))
    )
    (net (code "138") (name "unconnected-(U$3-Pad11)") (class "Default")
      (node (ref "U$3") (pin "11") (pinfunction "11_11") (pintype "passive"))
    )
    (net (code "139") (name "unconnected-(U$3-Pad12)") (class "Default")
      (node (ref "U$3") (pin "12") (pinfunction "12_12") (pintype "passive"))
    )
    (net (code "140") (name "unconnected-(U$4-Pad1_RESERVED)") (class "Default")
      (node (ref "U$4") (pin "1_RESERVED") (pinfunction "1_RESERVED_1_RESERVED") (pintype "bidirectional"))
    )
    (net (code "141") (name "unconnected-(U$4-Pad2_SS_N)") (class "Default")
      (node (ref "U$4") (pin "2_SS_N") (pinfunction "2_SS_N_2_SS_N") (pintype "bidirectional"))
    )
    (net (code "142") (name "unconnected-(U$4-Pad4_EXTINT0)") (class "Default")
      (node (ref "U$4") (pin "4_EXTINT0") (pinfunction "4_EXTINT0_4_EXTINT0") (pintype "bidirectional"))
    )
    (net (code "143") (name "unconnected-(U$4-Pad5_USB_DM)") (class "Default")
      (node (ref "U$4") (pin "5_USB_DM") (pinfunction "5_USB_DM_5_USB_DM") (pintype "bidirectional"))
    )
    (net (code "144") (name "unconnected-(U$4-Pad6_USB_DP)") (class "Default")
      (node (ref "U$4") (pin "6_USB_DP") (pinfunction "6_USB_DP_6_USB_DP") (pintype "bidirectional"))
    )
    (net (code "145") (name "unconnected-(U$4-Pad7_VDDUSB)") (class "Default")
      (node (ref "U$4") (pin "7_VDDUSB") (pinfunction "7_VDDUSB_7_VDDUSB") (pintype "bidirectional"))
    )
    (net (code "146") (name "unconnected-(U$4-Pad14_MOSI{slash}CFG_COM0)") (class "Default")
      (node (ref "U$4") (pin "14_MOSI/CFG_COM0") (pinfunction "14_MOSI/CFG_COM0_14_MOSI/CFG_COM0") (pintype "bidirectional"))
    )
    (net (code "147") (name "unconnected-(U$4-Pad15_MISO{slash}CFG_COM1)") (class "Default")
      (node (ref "U$4") (pin "15_MISO/CFG_COM1") (pinfunction "15_MISO/CFG_COM1_15_MISO/CFG_COM1") (pintype "bidirectional"))
    )
    (net (code "148") (name "unconnected-(U$4-Pad16_CFG_CPS0{slash}SCK)") (class "Default")
      (node (ref "U$4") (pin "16_CFG_CPS0/SCK") (pinfunction "16_CFG_CPS0/SCK_16_CFG_CPS0/SCK") (pintype "bidirectional"))
    )
    (net (code "149") (name "unconnected-(U$4-Pad17_RESERVED)") (class "Default")
      (node (ref "U$4") (pin "17_RESERVED") (pinfunction "17_RESERVED_17_RESERVED") (pintype "bidirectional"))
    )
    (net (code "150") (name "unconnected-(U$5-27-ID_SD-Pad27)") (class "Default")
      (node (ref "U$5") (pin "27") (pinfunction "27-ID_SD_27") (pintype "bidirectional"))
    )
    (net (code "151") (name "unconnected-(U$5-28-ID_SC-Pad28)") (class "Default")
      (node (ref "U$5") (pin "28") (pinfunction "28-ID_SC_28") (pintype "bidirectional"))
    )
    (net (code "152") (name "unconnected-(U$5-29-GPIO5-Pad29)") (class "Default")
      (node (ref "U$5") (pin "29") (pinfunction "29-GPIO5_29") (pintype "bidirectional"))
    )
    (net (code "153") (name "unconnected-(U$5-31-GPIO6-Pad31)") (class "Default")
      (node (ref "U$5") (pin "31") (pinfunction "31-GPIO6_31") (pintype "bidirectional"))
    )
    (net (code "154") (name "unconnected-(U$5-32-GPIO12-Pad32)") (class "Default")
      (node (ref "U$5") (pin "32") (pinfunction "32-GPIO12_32") (pintype "bidirectional"))
    )
    (net (code "155") (name "unconnected-(U$5-33-GPIO13-Pad33)") (class "Default")
      (node (ref "U$5") (pin "33") (pinfunction "33-GPIO13_33") (pintype "bidirectional"))
    )
    (net (code "156") (name "unconnected-(U$5-35-GPIO19-Pad35)") (class "Default")
      (node (ref "U$5") (pin "35") (pinfunction "35-GPIO19_35") (pintype "bidirectional"))
    )
    (net (code "157") (name "unconnected-(U$5-36-GPIO16-Pad36)") (class "Default")
      (node (ref "U$5") (pin "36") (pinfunction "36-GPIO16_36") (pintype "bidirectional"))
    )
    (net (code "158") (name "unconnected-(U$5-37-GPIO26-Pad37)") (class "Default")
      (node (ref "U$5") (pin "37") (pinfunction "37-GPIO26_37") (pintype "bidirectional"))
    )
    (net (code "159") (name "unconnected-(U$5-38-GPIO20-Pad38)") (class "Default")
      (node (ref "U$5") (pin "38") (pinfunction "38-GPIO20_38") (pintype "bidirectional"))
    )
    (net (code "160") (name "unconnected-(U$5-40-GPIO21-Pad40)") (class "Default")
      (node (ref "U$5") (pin "40") (pinfunction "40-GPIO21_40") (pintype "bidirectional"))
    )
    (net (code "161") (name "unconnected-(X1A-S-Pad1)") (class "Default")
      (node (ref "X1") (pin "1") (pinfunction "S_1") (pintype "passive"))
    )
    (net (code "162") (name "unconnected-(X1AA-S-Pad33)") (class "Default")
      (node (ref "X1") (pin "33") (pinfunction "S_33") (pintype "passive"))
    )
    (net (code "163") (name "unconnected-(X1AD-S-Pad36)") (class "Default")
      (node (ref "X1") (pin "36") (pinfunction "S_36") (pintype "passive"))
    )
    (net (code "164") (name "unconnected-(X1AF-S-Pad38)") (class "Default")
      (node (ref "X1") (pin "38") (pinfunction "S_38") (pintype "passive"))
    )
    (net (code "165") (name "unconnected-(X1AK-S-Pad42)") (class "Default")
      (node (ref "X1") (pin "42") (pinfunction "S_42") (pintype "passive"))
    )
    (net (code "166") (name "unconnected-(X1AM-S-Pad44)") (class "Default")
      (node (ref "X1") (pin "44") (pinfunction "S_44") (pintype "passive"))
    )
    (net (code "167") (name "unconnected-(X1AO-S-Pad46)") (class "Default")
      (node (ref "X1") (pin "46") (pinfunction "S_46") (pintype "passive"))
    )
    (net (code "168") (name "unconnected-(X1AQ-S-Pad48)") (class "Default")
      (node (ref "X1") (pin "48") (pinfunction "S_48") (pintype "passive"))
    )
    (net (code "169") (name "unconnected-(X1AS-S-Pad5)") (class "Default")
      (node (ref "X1") (pin "5") (pinfunction "S_5") (pintype "passive"))
    )
    (net (code "170") (name "unconnected-(X1AW-S-Pad6)") (class "Default")
      (node (ref "X1") (pin "6") (pinfunction "S_6") (pintype "passive"))
    )
    (net (code "171") (name "unconnected-(X1AX-S-Pad7)") (class "Default")
      (node (ref "X1") (pin "7") (pinfunction "S_7") (pintype "passive"))
    )
    (net (code "172") (name "unconnected-(X1AY-S-Pad8)") (class "Default")
      (node (ref "X1") (pin "8") (pinfunction "S_8") (pintype "passive"))
    )
    (net (code "173") (name "unconnected-(X1B-S-Pad10)") (class "Default")
      (node (ref "X1") (pin "10") (pinfunction "S_10") (pintype "passive"))
    )
    (net (code "174") (name "unconnected-(X1C-S-Pad11)") (class "Default")
      (node (ref "X1") (pin "11") (pinfunction "S_11") (pintype "passive"))
    )
    (net (code "175") (name "unconnected-(X1D-S-Pad12)") (class "Default")
      (node (ref "X1") (pin "12") (pinfunction "S_12") (pintype "passive"))
    )
    (net (code "176") (name "unconnected-(X1E-S-Pad13)") (class "Default")
      (node (ref "X1") (pin "13") (pinfunction "S_13") (pintype "passive"))
    )
    (net (code "177") (name "unconnected-(X1F-S-Pad14)") (class "Default")
      (node (ref "X1") (pin "14") (pinfunction "S_14") (pintype "passive"))
    )
    (net (code "178") (name "unconnected-(X1H-S-Pad16)") (class "Default")
      (node (ref "X1") (pin "16") (pinfunction "S_16") (pintype "passive"))
    )
    (net (code "179") (name "unconnected-(X1M-S-Pad20)") (class "Default")
      (node (ref "X1") (pin "20") (pinfunction "S_20") (pintype "passive"))
    )
    (net (code "180") (name "unconnected-(X1P-S-Pad23)") (class "Default")
      (node (ref "X1") (pin "23") (pinfunction "S_23") (pintype "passive"))
    )
    (net (code "181") (name "unconnected-(X1R-S-Pad25)") (class "Default")
      (node (ref "X1") (pin "25") (pinfunction "S_25") (pintype "passive"))
    )
    (net (code "182") (name "unconnected-(X1U-S-Pad28)") (class "Default")
      (node (ref "X1") (pin "28") (pinfunction "S_28") (pintype "passive"))
    )
    (net (code "183") (name "unconnected-(X1W-S-Pad3)") (class "Default")
      (node (ref "X1") (pin "3") (pinfunction "S_3") (pintype "passive"))
    )
    (net (code "184") (name "unconnected-(X1X-S-Pad30)") (class "Default")
      (node (ref "X1") (pin "30") (pinfunction "S_30") (pintype "passive"))
    )
    (net (code "185") (name "unconnected-(X1Y-S-Pad31)") (class "Default")
      (node (ref "X1") (pin "31") (pinfunction "S_31") (pintype "passive"))
    )
    (net (code "186") (name "unconnected-(X1Z-S-Pad32)") (class "Default")
      (node (ref "X1") (pin "32") (pinfunction "S_32") (pintype "passive"))
    )
    (net (code "187") (name "unconnected-(X2A-S-Pad1)") (class "Default")
      (node (ref "X2") (pin "1") (pinfunction "S_1") (pintype "passive"))
    )
    (net (code "188") (name "unconnected-(X2AA-S-Pad33)") (class "Default")
      (node (ref "X2") (pin "33") (pinfunction "S_33") (pintype "passive"))
    )
    (net (code "189") (name "unconnected-(X2AK-S-Pad42)") (class "Default")
      (node (ref "X2") (pin "42") (pinfunction "S_42") (pintype "passive"))
    )
    (net (code "190") (name "unconnected-(X2AM-S-Pad44)") (class "Default")
      (node (ref "X2") (pin "44") (pinfunction "S_44") (pintype "passive"))
    )
    (net (code "191") (name "unconnected-(X2AN-S-Pad45)") (class "Default")
      (node (ref "X2") (pin "45") (pinfunction "S_45") (pintype "passive"))
    )
    (net (code "192") (name "unconnected-(X2AO-S-Pad46)") (class "Default")
      (node (ref "X2") (pin "46") (pinfunction "S_46") (pintype "passive"))
    )
    (net (code "193") (name "unconnected-(X2AP-S-Pad47)") (class "Default")
      (node (ref "X2") (pin "47") (pinfunction "S_47") (pintype "passive"))
    )
    (net (code "194") (name "unconnected-(X2AR-S-Pad49)") (class "Default")
      (node (ref "X2") (pin "49") (pinfunction "S_49") (pintype "passive"))
    )
    (net (code "195") (name "unconnected-(X2AS-S-Pad5)") (class "Default")
      (node (ref "X2") (pin "5") (pinfunction "S_5") (pintype "passive"))
    )
    (net (code "196") (name "unconnected-(X2AU-S-Pad51)") (class "Default")
      (node (ref "X2") (pin "51") (pinfunction "S_51") (pintype "passive"))
    )
    (net (code "197") (name "unconnected-(X2AX-S-Pad7)") (class "Default")
      (node (ref "X2") (pin "7") (pinfunction "S_7") (pintype "passive"))
    )
    (net (code "198") (name "unconnected-(X2C-S-Pad11)") (class "Default")
      (node (ref "X2") (pin "11") (pinfunction "S_11") (pintype "passive"))
    )
    (net (code "199") (name "unconnected-(X2E-S-Pad13)") (class "Default")
      (node (ref "X2") (pin "13") (pinfunction "S_13") (pintype "passive"))
    )
    (net (code "200") (name "unconnected-(X2H-S-Pad16)") (class "Default")
      (node (ref "X2") (pin "16") (pinfunction "S_16") (pintype "passive"))
    )
    (net (code "201") (name "unconnected-(X2K-S-Pad19)") (class "Default")
      (node (ref "X2") (pin "19") (pinfunction "S_19") (pintype "passive"))
    )
    (net (code "202") (name "unconnected-(X2M-S-Pad20)") (class "Default")
      (node (ref "X2") (pin "20") (pinfunction "S_20") (pintype "passive"))
    )
    (net (code "203") (name "unconnected-(X2O-S-Pad22)") (class "Default")
      (node (ref "X2") (pin "22") (pinfunction "S_22") (pintype "passive"))
    )
    (net (code "204") (name "unconnected-(X2P-S-Pad23)") (class "Default")
      (node (ref "X2") (pin "23") (pinfunction "S_23") (pintype "passive"))
    )
    (net (code "205") (name "unconnected-(X2R-S-Pad25)") (class "Default")
      (node (ref "X2") (pin "25") (pinfunction "S_25") (pintype "passive"))
    )
    (net (code "206") (name "unconnected-(X2W-S-Pad3)") (class "Default")
      (node (ref "X2") (pin "3") (pinfunction "S_3") (pintype "passive"))
    )
    (net (code "207") (name "unconnected-(X2Y-S-Pad31)") (class "Default")
      (node (ref "X2") (pin "31") (pinfunction "S_31") (pintype "passive"))
    )
    (net (code "208") (name "unconnected-(X3A-S-Pad1)") (class "Default")
      (node (ref "X3") (pin "1") (pinfunction "S_1") (pintype "passive"))
    )
    (net (code "209") (name "unconnected-(X3AA-S-Pad33)") (class "Default")
      (node (ref "X3") (pin "33") (pinfunction "S_33") (pintype "passive"))
    )
    (net (code "210") (name "unconnected-(X3AD-S-Pad36)") (class "Default")
      (node (ref "X3") (pin "36") (pinfunction "S_36") (pintype "passive"))
    )
    (net (code "211") (name "unconnected-(X3AF-S-Pad38)") (class "Default")
      (node (ref "X3") (pin "38") (pinfunction "S_38") (pintype "passive"))
    )
    (net (code "212") (name "unconnected-(X3AK-S-Pad42)") (class "Default")
      (node (ref "X3") (pin "42") (pinfunction "S_42") (pintype "passive"))
    )
    (net (code "213") (name "unconnected-(X3AM-S-Pad44)") (class "Default")
      (node (ref "X3") (pin "44") (pinfunction "S_44") (pintype "passive"))
    )
    (net (code "214") (name "unconnected-(X3AO-S-Pad46)") (class "Default")
      (node (ref "X3") (pin "46") (pinfunction "S_46") (pintype "passive"))
    )
    (net (code "215") (name "unconnected-(X3AQ-S-Pad48)") (class "Default")
      (node (ref "X3") (pin "48") (pinfunction "S_48") (pintype "passive"))
    )
    (net (code "216") (name "unconnected-(X3AS-S-Pad5)") (class "Default")
      (node (ref "X3") (pin "5") (pinfunction "S_5") (pintype "passive"))
    )
    (net (code "217") (name "unconnected-(X3AW-S-Pad6)") (class "Default")
      (node (ref "X3") (pin "6") (pinfunction "S_6") (pintype "passive"))
    )
    (net (code "218") (name "unconnected-(X3AX-S-Pad7)") (class "Default")
      (node (ref "X3") (pin "7") (pinfunction "S_7") (pintype "passive"))
    )
    (net (code "219") (name "unconnected-(X3AY-S-Pad8)") (class "Default")
      (node (ref "X3") (pin "8") (pinfunction "S_8") (pintype "passive"))
    )
    (net (code "220") (name "unconnected-(X3B-S-Pad10)") (class "Default")
      (node (ref "X3") (pin "10") (pinfunction "S_10") (pintype "passive"))
    )
    (net (code "221") (name "unconnected-(X3C-S-Pad11)") (class "Default")
      (node (ref "X3") (pin "11") (pinfunction "S_11") (pintype "passive"))
    )
    (net (code "222") (name "unconnected-(X3D-S-Pad12)") (class "Default")
      (node (ref "X3") (pin "12") (pinfunction "S_12") (pintype "passive"))
    )
    (net (code "223") (name "unconnected-(X3E-S-Pad13)") (class "Default")
      (node (ref "X3") (pin "13") (pinfunction "S_13") (pintype "passive"))
    )
    (net (code "224") (name "unconnected-(X3F-S-Pad14)") (class "Default")
      (node (ref "X3") (pin "14") (pinfunction "S_14") (pintype "passive"))
    )
    (net (code "225") (name "unconnected-(X3H-S-Pad16)") (class "Default")
      (node (ref "X3") (pin "16") (pinfunction "S_16") (pintype "passive"))
    )
    (net (code "226") (name "unconnected-(X3M-S-Pad20)") (class "Default")
      (node (ref "X3") (pin "20") (pinfunction "S_20") (pintype "passive"))
    )
    (net (code "227") (name "unconnected-(X3P-S-Pad23)") (class "Default")
      (node (ref "X3") (pin "23") (pinfunction "S_23") (pintype "passive"))
    )
    (net (code "228") (name "unconnected-(X3R-S-Pad25)") (class "Default")
      (node (ref "X3") (pin "25") (pinfunction "S_25") (pintype "passive"))
    )
    (net (code "229") (name "unconnected-(X3U-S-Pad28)") (class "Default")
      (node (ref "X3") (pin "28") (pinfunction "S_28") (pintype "passive"))
    )
    (net (code "230") (name "unconnected-(X3W-S-Pad3)") (class "Default")
      (node (ref "X3") (pin "3") (pinfunction "S_3") (pintype "passive"))
    )
    (net (code "231") (name "unconnected-(X3X-S-Pad30)") (class "Default")
      (node (ref "X3") (pin "30") (pinfunction "S_30") (pintype "passive"))
    )
    (net (code "232") (name "unconnected-(X3Y-S-Pad31)") (class "Default")
      (node (ref "X3") (pin "31") (pinfunction "S_31") (pintype "passive"))
    )
    (net (code "233") (name "unconnected-(X3Z-S-Pad32)") (class "Default")
      (node (ref "X3") (pin "32") (pinfunction "S_32") (pintype "passive"))
    )
  )
)
